# 1500015_ICLED_Featherwing_HW-V1-0.net
KiCad netlist of a schematic drawn in EAGLE
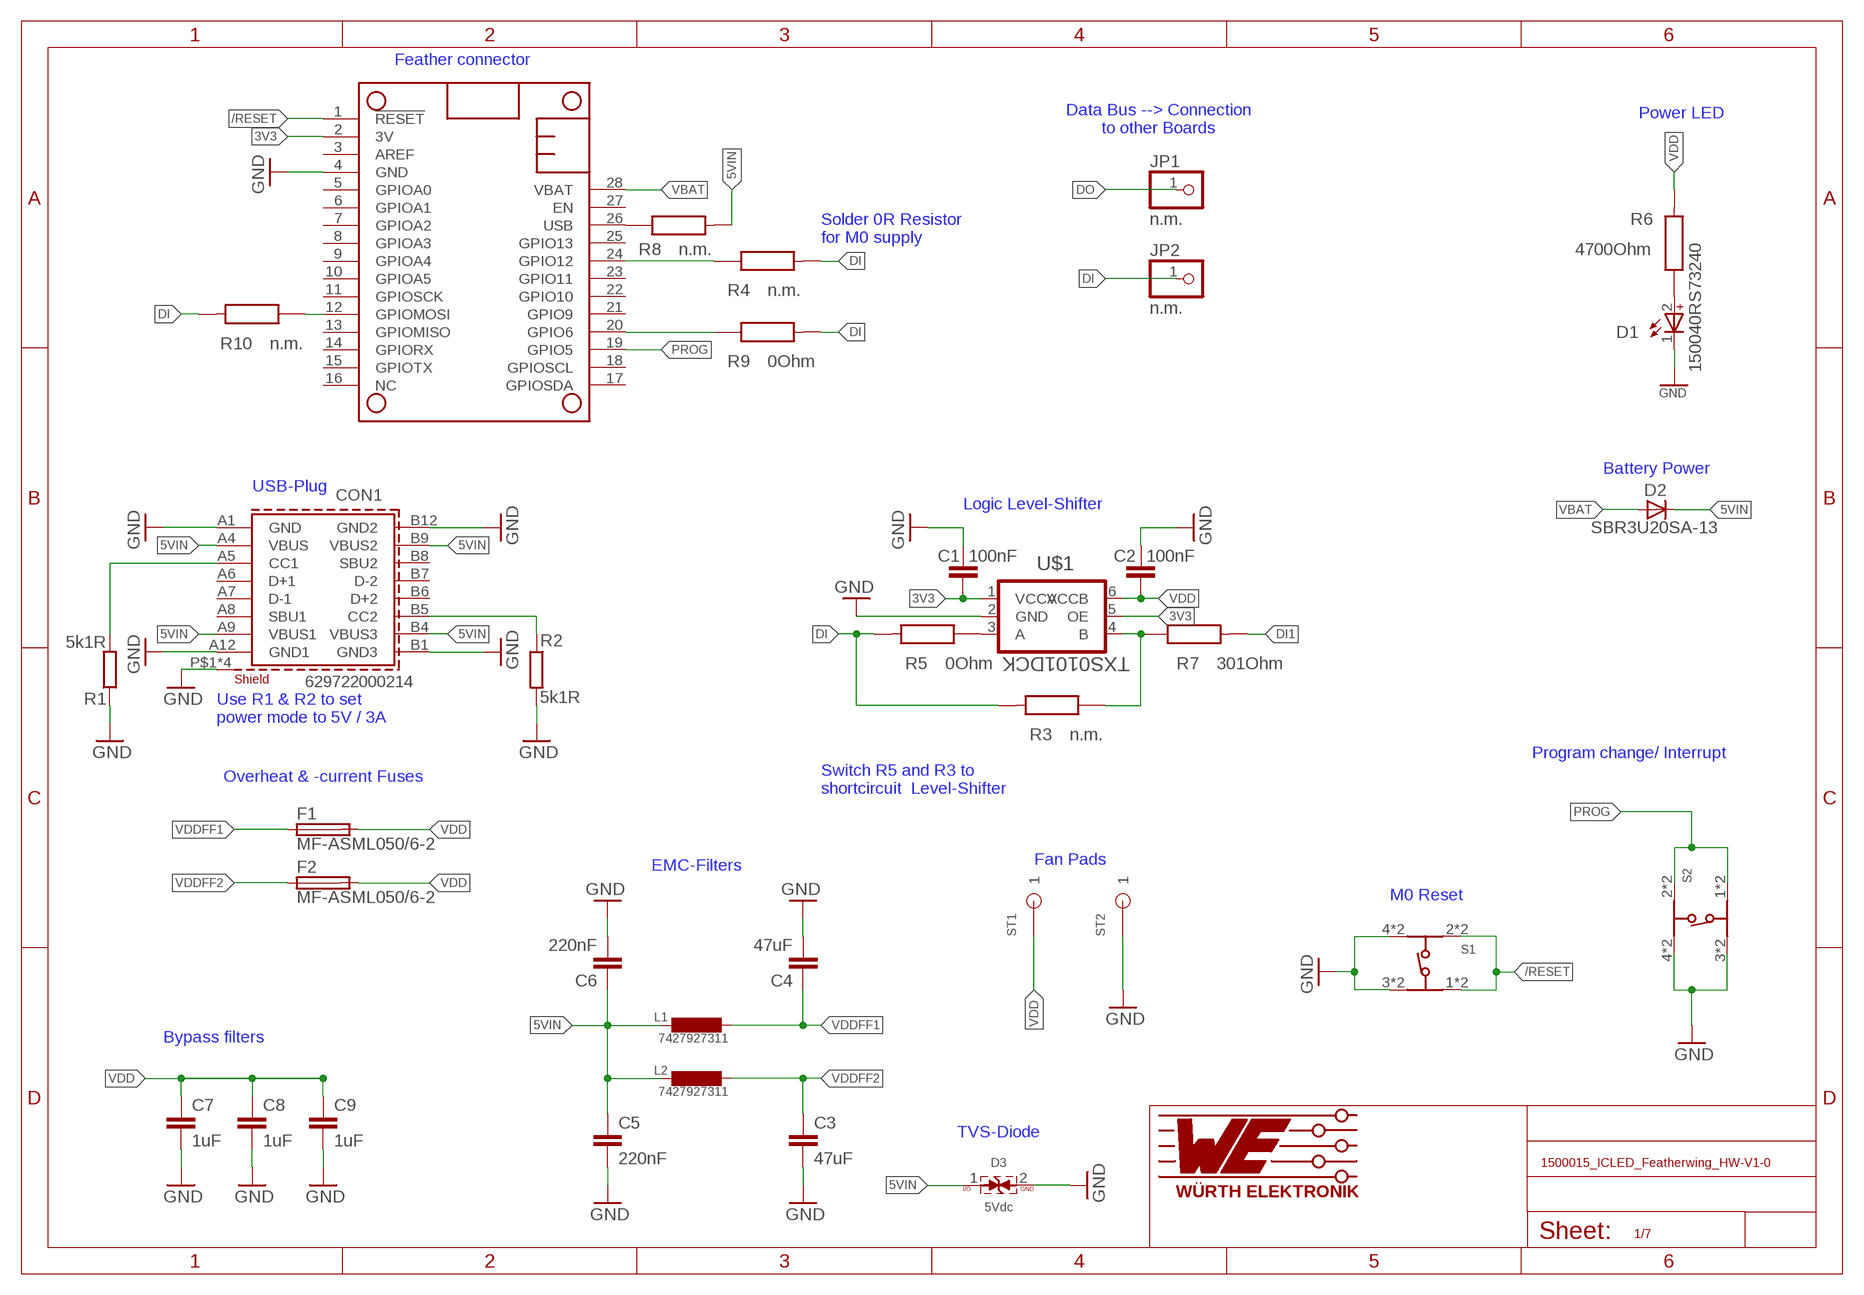
[diagram p0: schematic, sheet 1]
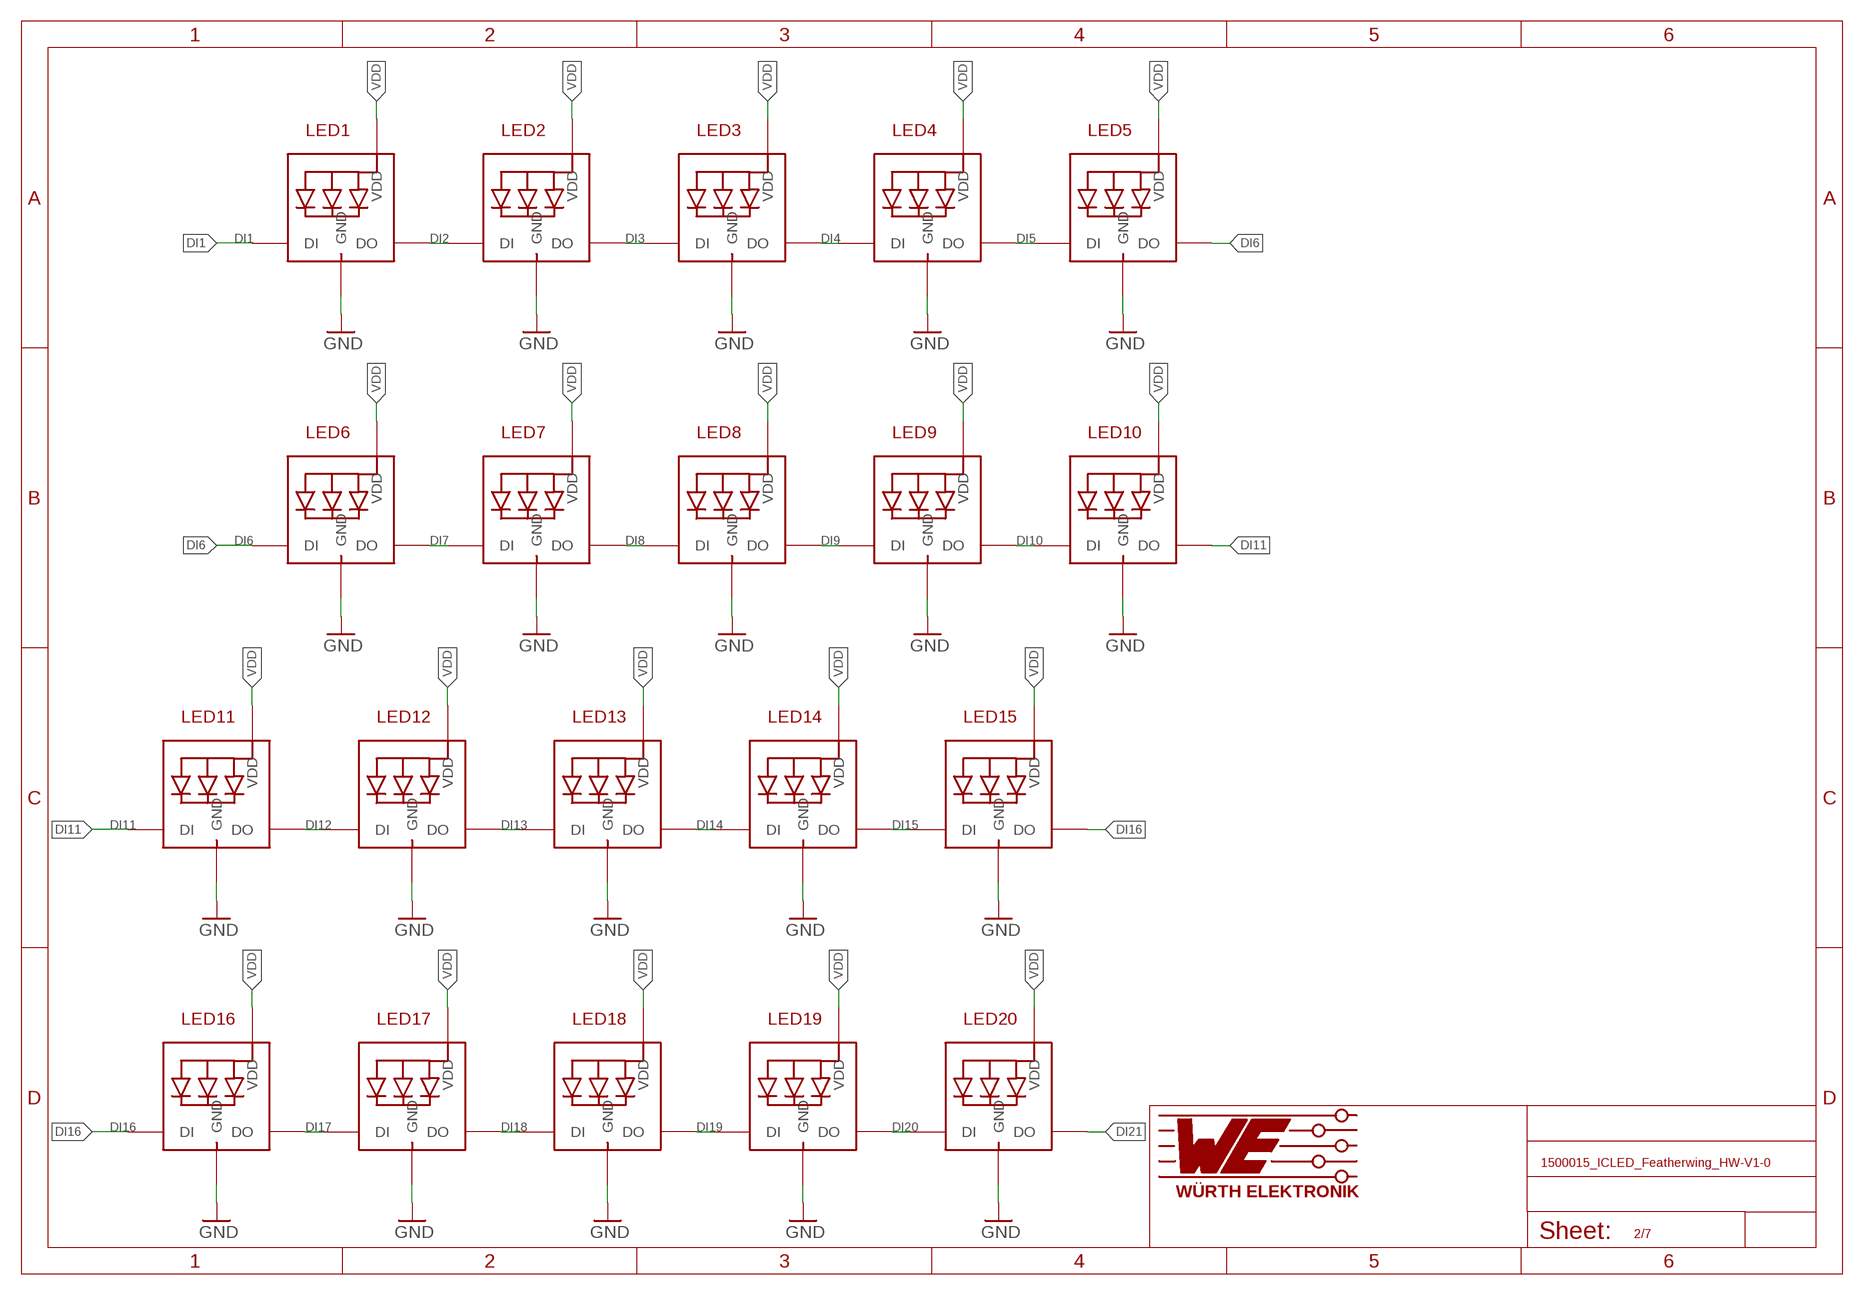
[diagram p1: schematic, sheet 2]
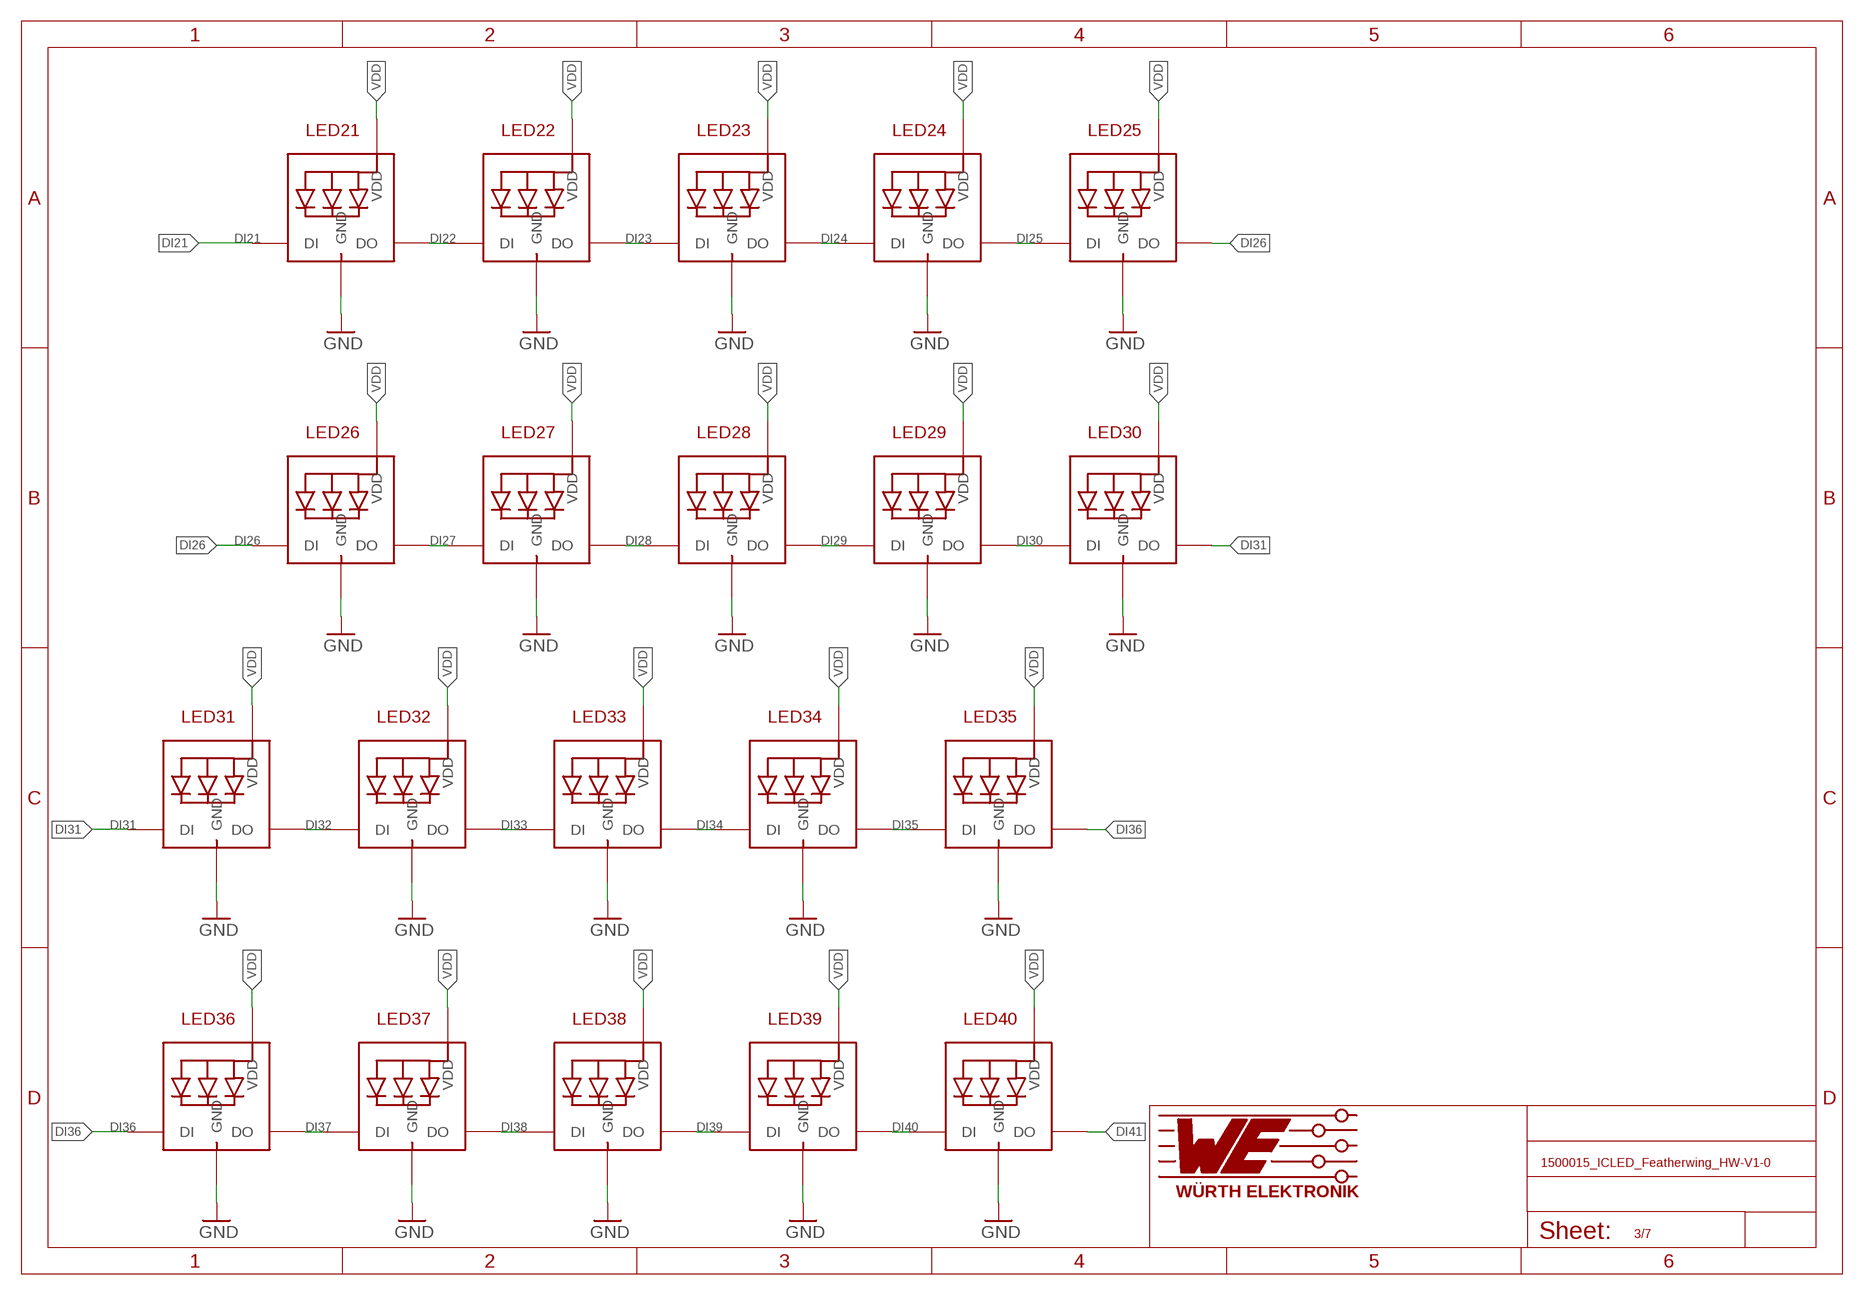
[diagram p2: schematic, sheet 3]
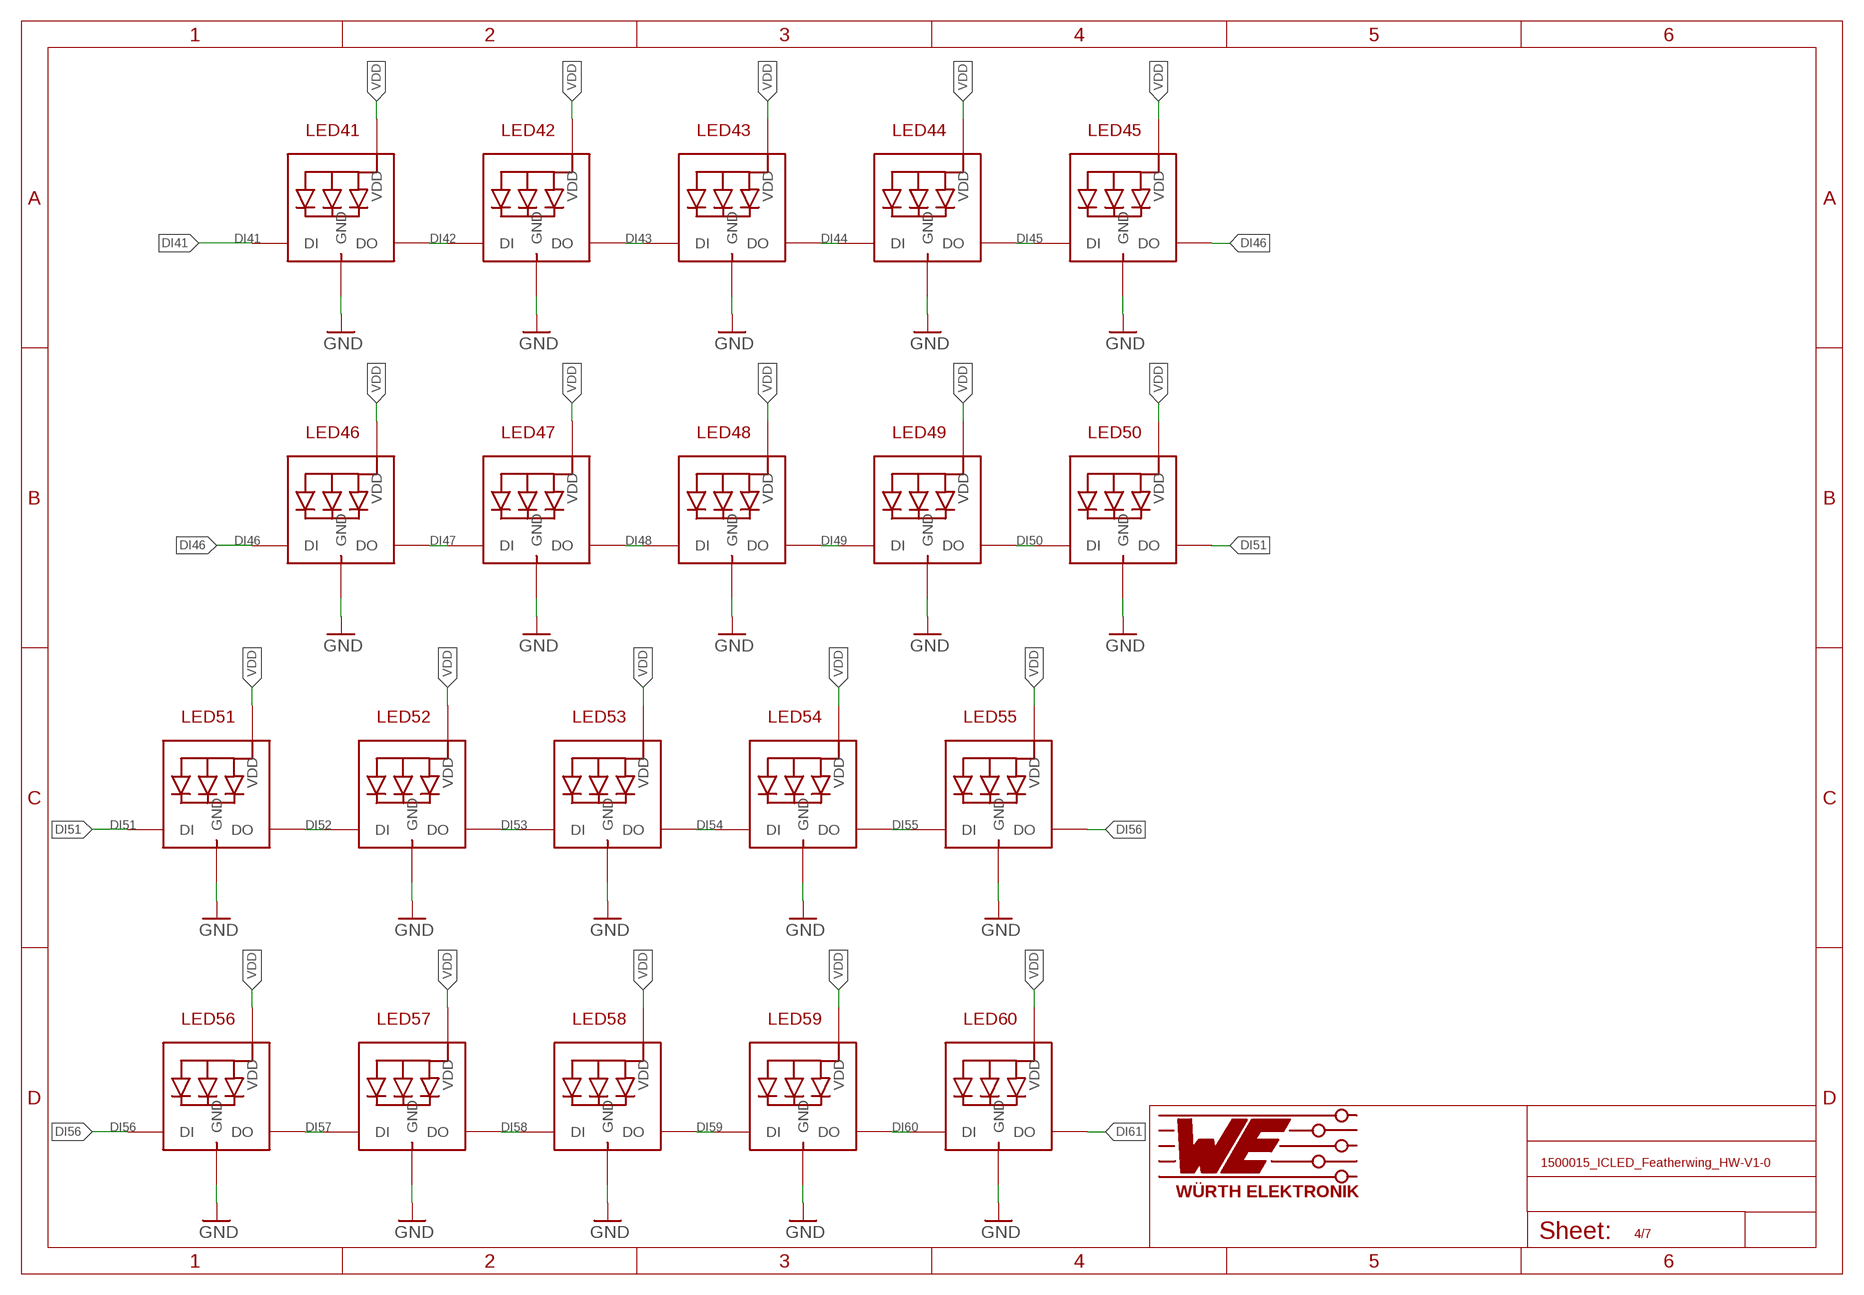
[diagram p3: schematic, sheet 4]
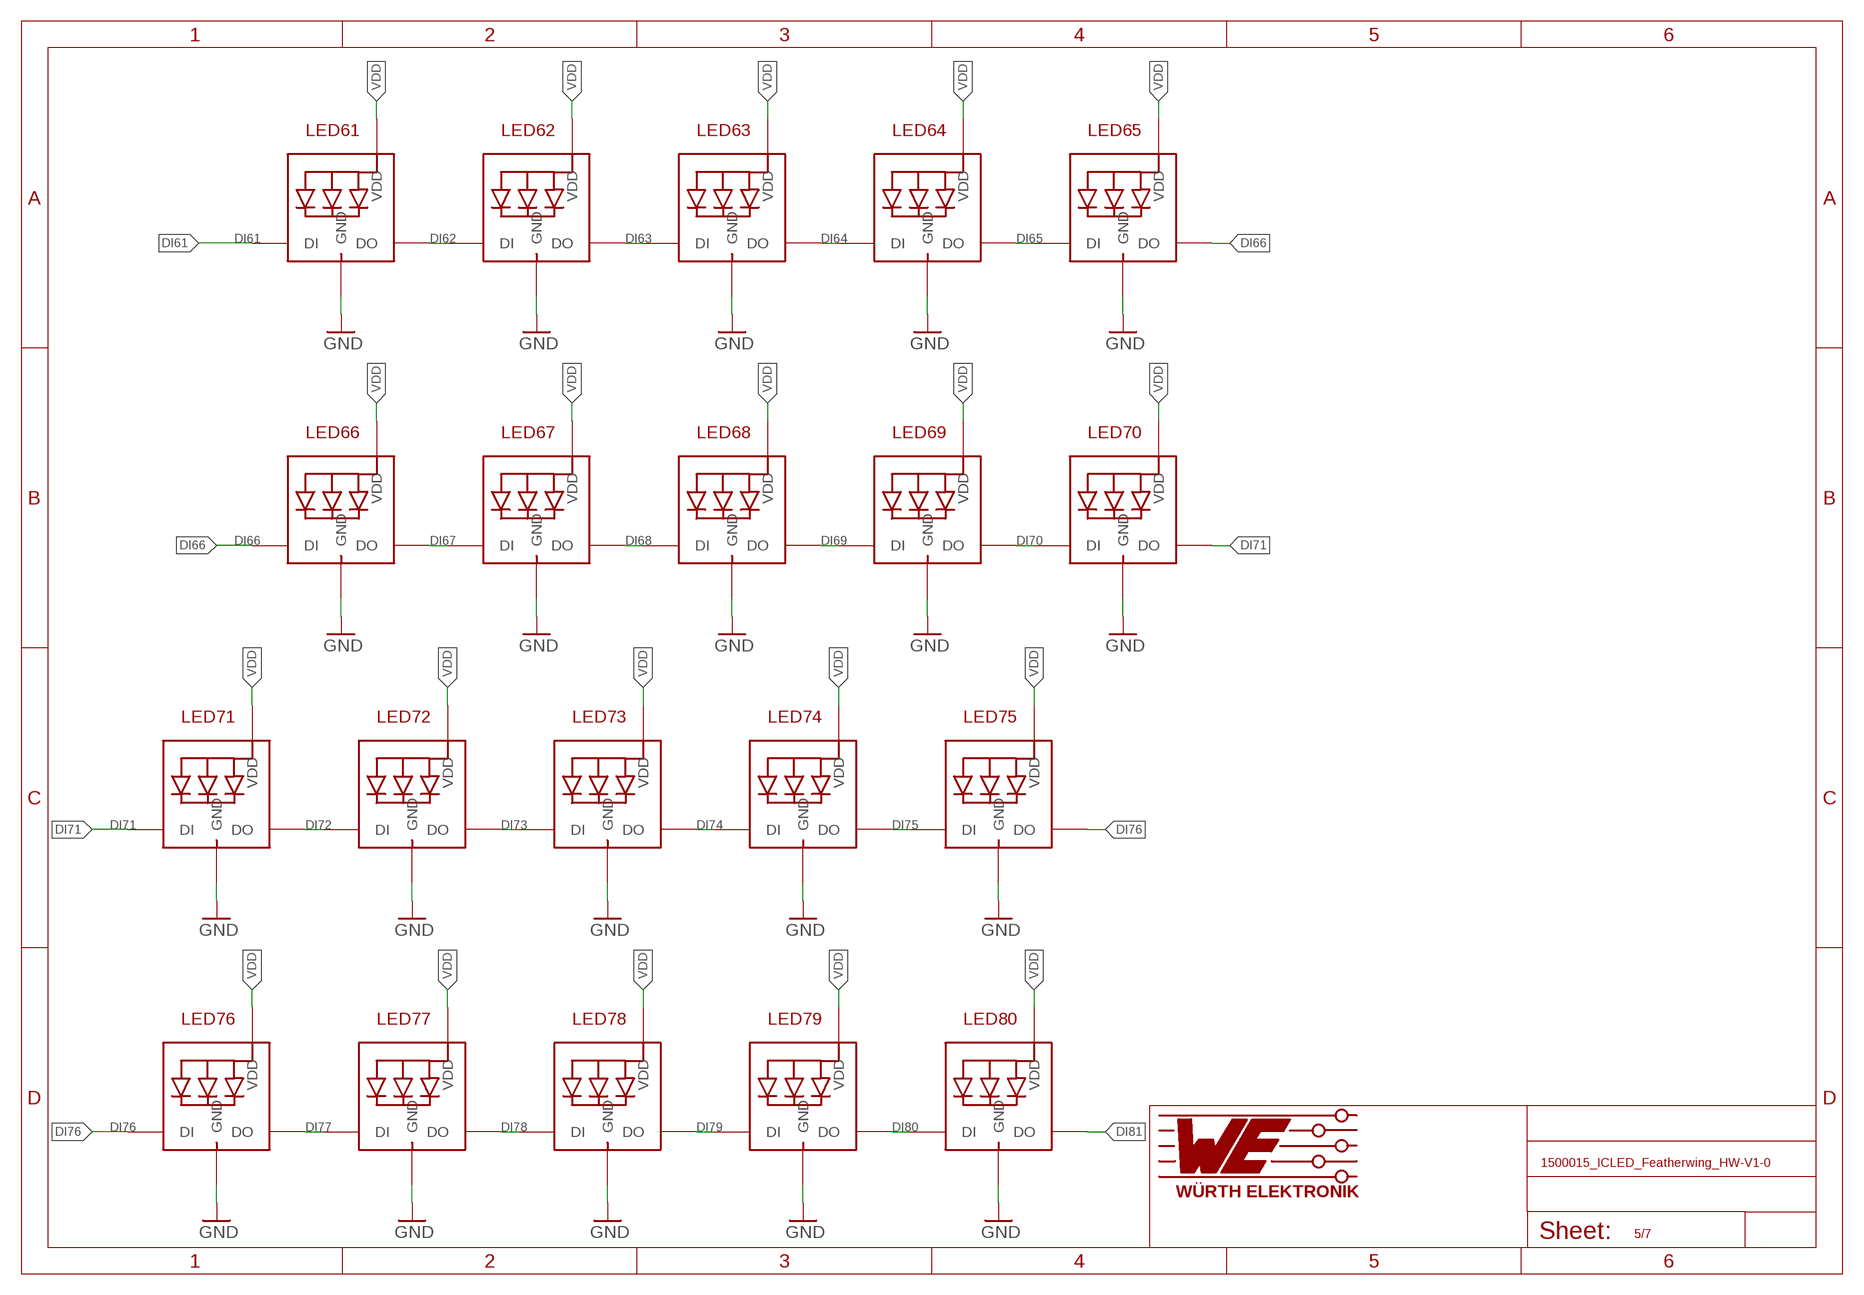
[diagram p4: schematic, sheet 5]
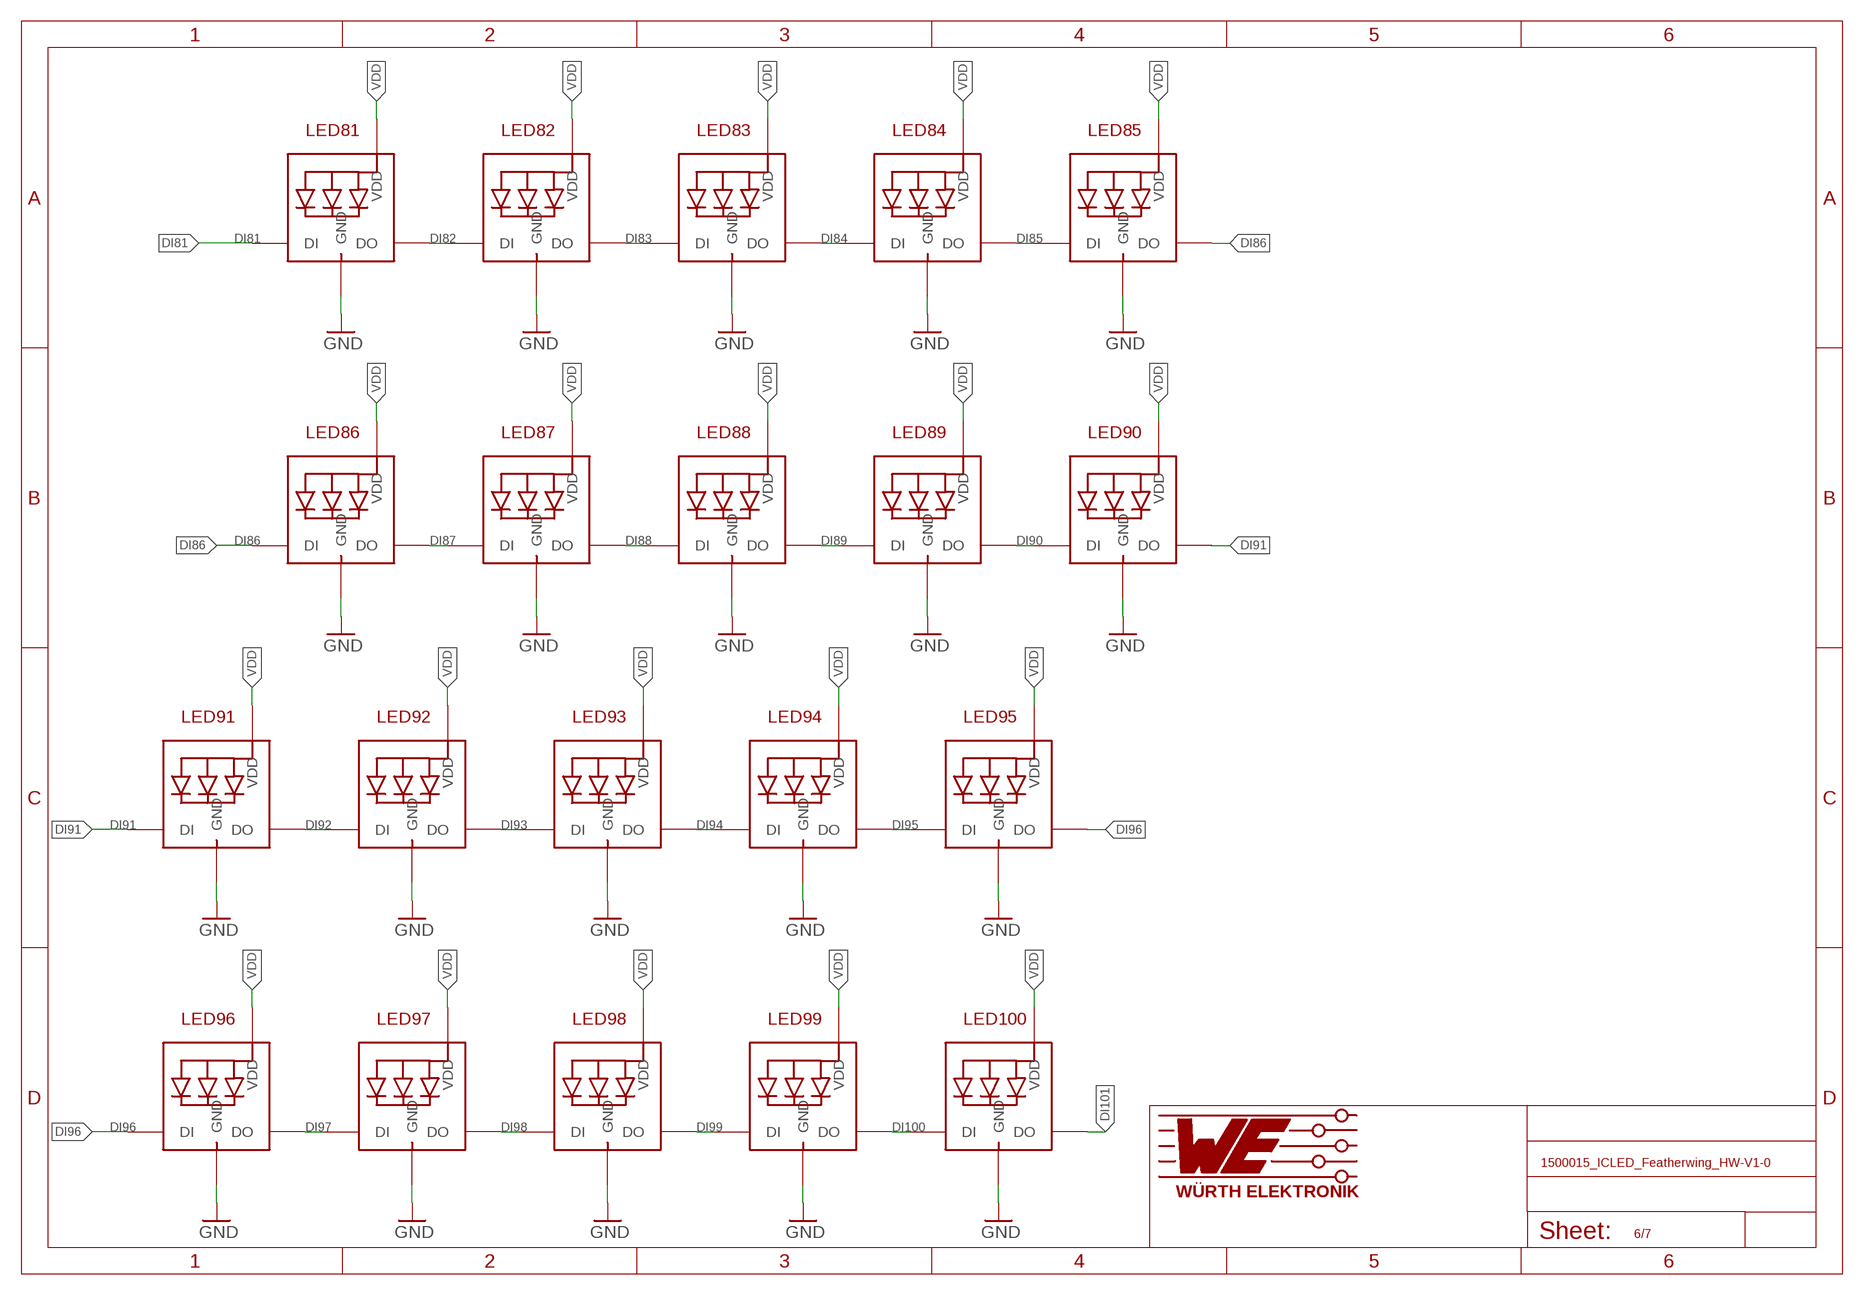
[diagram p5: schematic, sheet 6]
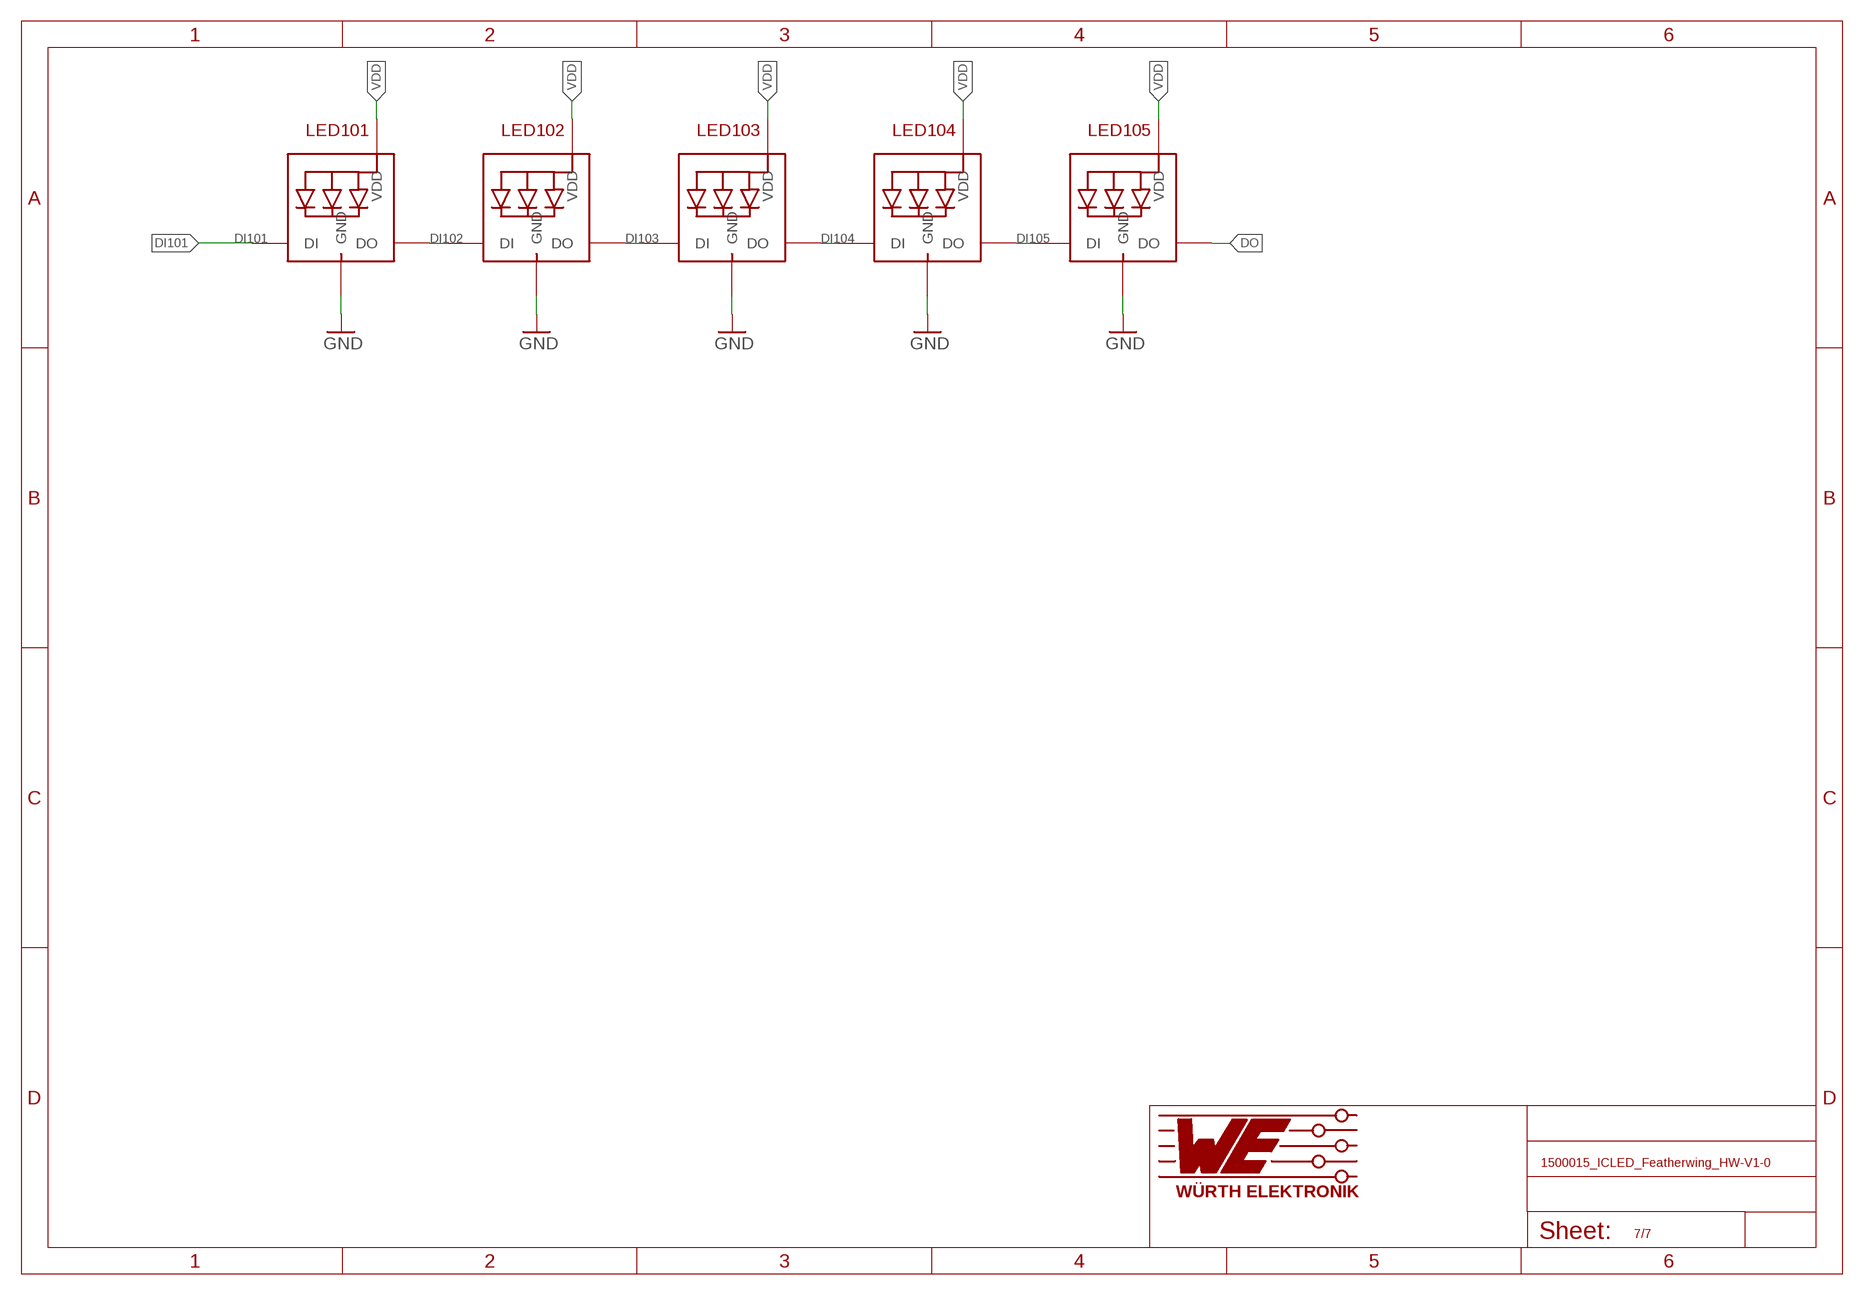
[diagram p6: schematic, sheet 7]

(export (version "E")
  (design (tool "Eeschema 10.0.6"))
  (components
    (comp (ref "LED41")
      (value "1312020030000")
      (footprint "eagle-import:1312020030000_FWANGEPASST")
      (fields (field (name "MANUFACTURER") "Würth Elektronik"))
      (libsource (lib "eagle-import") (part "1312020030000"))
    )
    (comp (ref "LED42")
      (value "1312020030000")
      (footprint "eagle-import:1312020030000_FWANGEPASST")
      (fields (field (name "MANUFACTURER") "Würth Elektronik"))
      (libsource (lib "eagle-import") (part "1312020030000"))
    )
    (comp (ref "LED43")
      (value "1312020030000")
      (footprint "eagle-import:1312020030000_FWANGEPASST")
      (fields (field (name "MANUFACTURER") "Würth Elektronik"))
      (libsource (lib "eagle-import") (part "1312020030000"))
    )
    (comp (ref "LED44")
      (value "1312020030000")
      (footprint "eagle-import:1312020030000_FWANGEPASST")
      (fields (field (name "MANUFACTURER") "Würth Elektronik"))
      (libsource (lib "eagle-import") (part "1312020030000"))
    )
    (comp (ref "LED45")
      (value "1312020030000")
      (footprint "eagle-import:1312020030000_FWANGEPASST")
      (fields (field (name "MANUFACTURER") "Würth Elektronik"))
      (libsource (lib "eagle-import") (part "1312020030000"))
    )
    (comp (ref "LED46")
      (value "1312020030000")
      (footprint "eagle-import:1312020030000_FWANGEPASST")
      (fields (field (name "MANUFACTURER") "Würth Elektronik"))
      (libsource (lib "eagle-import") (part "1312020030000"))
    )
    (comp (ref "LED47")
      (value "1312020030000")
      (footprint "eagle-import:1312020030000_FWANGEPASST")
      (fields (field (name "MANUFACTURER") "Würth Elektronik"))
      (libsource (lib "eagle-import") (part "1312020030000"))
    )
    (comp (ref "LED48")
      (value "1312020030000")
      (footprint "eagle-import:1312020030000_FWANGEPASST")
      (fields (field (name "MANUFACTURER") "Würth Elektronik"))
      (libsource (lib "eagle-import") (part "1312020030000"))
    )
    (comp (ref "LED49")
      (value "1312020030000")
      (footprint "eagle-import:1312020030000_FWANGEPASST")
      (fields (field (name "MANUFACTURER") "Würth Elektronik"))
      (libsource (lib "eagle-import") (part "1312020030000"))
    )
    (comp (ref "LED50")
      (value "1312020030000")
      (footprint "eagle-import:1312020030000_FWANGEPASST")
      (fields (field (name "MANUFACTURER") "Würth Elektronik"))
      (libsource (lib "eagle-import") (part "1312020030000"))
    )
    (comp (ref "LED51")
      (value "1312020030000")
      (footprint "eagle-import:1312020030000_FWANGEPASST")
      (fields (field (name "MANUFACTURER") "Würth Elektronik"))
      (libsource (lib "eagle-import") (part "1312020030000"))
    )
    (comp (ref "LED52")
      (value "1312020030000")
      (footprint "eagle-import:1312020030000_FWANGEPASST")
      (fields (field (name "MANUFACTURER") "Würth Elektronik"))
      (libsource (lib "eagle-import") (part "1312020030000"))
    )
    (comp (ref "LED53")
      (value "1312020030000")
      (footprint "eagle-import:1312020030000_FWANGEPASST")
      (fields (field (name "MANUFACTURER") "Würth Elektronik"))
      (libsource (lib "eagle-import") (part "1312020030000"))
    )
    (comp (ref "LED54")
      (value "1312020030000")
      (footprint "eagle-import:1312020030000_FWANGEPASST")
      (fields (field (name "MANUFACTURER") "Würth Elektronik"))
      (libsource (lib "eagle-import") (part "1312020030000"))
    )
    (comp (ref "LED55")
      (value "1312020030000")
      (footprint "eagle-import:1312020030000_FWANGEPASST")
      (fields (field (name "MANUFACTURER") "Würth Elektronik"))
      (libsource (lib "eagle-import") (part "1312020030000"))
    )
    (comp (ref "LED56")
      (value "1312020030000")
      (footprint "eagle-import:1312020030000_FWANGEPASST")
      (fields (field (name "MANUFACTURER") "Würth Elektronik"))
      (libsource (lib "eagle-import") (part "1312020030000"))
    )
    (comp (ref "LED57")
      (value "1312020030000")
      (footprint "eagle-import:1312020030000_FWANGEPASST")
      (fields (field (name "MANUFACTURER") "Würth Elektronik"))
      (libsource (lib "eagle-import") (part "1312020030000"))
    )
    (comp (ref "LED58")
      (value "1312020030000")
      (footprint "eagle-import:1312020030000_FWANGEPASST")
      (fields (field (name "MANUFACTURER") "Würth Elektronik"))
      (libsource (lib "eagle-import") (part "1312020030000"))
    )
    (comp (ref "LED59")
      (value "1312020030000")
      (footprint "eagle-import:1312020030000_FWANGEPASST")
      (fields (field (name "MANUFACTURER") "Würth Elektronik"))
      (libsource (lib "eagle-import") (part "1312020030000"))
    )
    (comp (ref "LED60")
      (value "1312020030000")
      (footprint "eagle-import:1312020030000_FWANGEPASST")
      (fields (field (name "MANUFACTURER") "Würth Elektronik"))
      (libsource (lib "eagle-import") (part "1312020030000"))
    )
    (comp (ref "LED61")
      (value "1312020030000")
      (footprint "eagle-import:1312020030000_FWANGEPASST")
      (fields (field (name "MANUFACTURER") "Würth Elektronik"))
      (libsource (lib "eagle-import") (part "1312020030000"))
    )
    (comp (ref "LED62")
      (value "1312020030000")
      (footprint "eagle-import:1312020030000_FWANGEPASST")
      (fields (field (name "MANUFACTURER") "Würth Elektronik"))
      (libsource (lib "eagle-import") (part "1312020030000"))
    )
    (comp (ref "LED63")
      (value "1312020030000")
      (footprint "eagle-import:1312020030000_FWANGEPASST")
      (fields (field (name "MANUFACTURER") "Würth Elektronik"))
      (libsource (lib "eagle-import") (part "1312020030000"))
    )
    (comp (ref "LED64")
      (value "1312020030000")
      (footprint "eagle-import:1312020030000_FWANGEPASST")
      (fields (field (name "MANUFACTURER") "Würth Elektronik"))
      (libsource (lib "eagle-import") (part "1312020030000"))
    )
    (comp (ref "LED65")
      (value "1312020030000")
      (footprint "eagle-import:1312020030000_FWANGEPASST")
      (fields (field (name "MANUFACTURER") "Würth Elektronik"))
      (libsource (lib "eagle-import") (part "1312020030000"))
    )
    (comp (ref "LED66")
      (value "1312020030000")
      (footprint "eagle-import:1312020030000_FWANGEPASST")
      (fields (field (name "MANUFACTURER") "Würth Elektronik"))
      (libsource (lib "eagle-import") (part "1312020030000"))
    )
    (comp (ref "LED67")
      (value "1312020030000")
      (footprint "eagle-import:1312020030000_FWANGEPASST")
      (fields (field (name "MANUFACTURER") "Würth Elektronik"))
      (libsource (lib "eagle-import") (part "1312020030000"))
    )
    (comp (ref "LED68")
      (value "1312020030000")
      (footprint "eagle-import:1312020030000_FWANGEPASST")
      (fields (field (name "MANUFACTURER") "Würth Elektronik"))
      (libsource (lib "eagle-import") (part "1312020030000"))
    )
    (comp (ref "LED69")
      (value "1312020030000")
      (footprint "eagle-import:1312020030000_FWANGEPASST")
      (fields (field (name "MANUFACTURER") "Würth Elektronik"))
      (libsource (lib "eagle-import") (part "1312020030000"))
    )
    (comp (ref "LED70")
      (value "1312020030000")
      (footprint "eagle-import:1312020030000_FWANGEPASST")
      (fields (field (name "MANUFACTURER") "Würth Elektronik"))
      (libsource (lib "eagle-import") (part "1312020030000"))
    )
    (comp (ref "LED71")
      (value "1312020030000")
      (footprint "eagle-import:1312020030000_FWANGEPASST")
      (fields (field (name "MANUFACTURER") "Würth Elektronik"))
      (libsource (lib "eagle-import") (part "1312020030000"))
    )
    (comp (ref "LED72")
      (value "1312020030000")
      (footprint "eagle-import:1312020030000_FWANGEPASST")
      (fields (field (name "MANUFACTURER") "Würth Elektronik"))
      (libsource (lib "eagle-import") (part "1312020030000"))
    )
    (comp (ref "LED73")
      (value "1312020030000")
      (footprint "eagle-import:1312020030000_FWANGEPASST")
      (fields (field (name "MANUFACTURER") "Würth Elektronik"))
      (libsource (lib "eagle-import") (part "1312020030000"))
    )
    (comp (ref "LED74")
      (value "1312020030000")
      (footprint "eagle-import:1312020030000_FWANGEPASST")
      (fields (field (name "MANUFACTURER") "Würth Elektronik"))
      (libsource (lib "eagle-import") (part "1312020030000"))
    )
    (comp (ref "LED75")
      (value "1312020030000")
      (footprint "eagle-import:1312020030000_FWANGEPASST")
      (fields (field (name "MANUFACTURER") "Würth Elektronik"))
      (libsource (lib "eagle-import") (part "1312020030000"))
    )
    (comp (ref "LED76")
      (value "1312020030000")
      (footprint "eagle-import:1312020030000_FWANGEPASST")
      (fields (field (name "MANUFACTURER") "Würth Elektronik"))
      (libsource (lib "eagle-import") (part "1312020030000"))
    )
    (comp (ref "LED77")
      (value "1312020030000")
      (footprint "eagle-import:1312020030000_FWANGEPASST")
      (fields (field (name "MANUFACTURER") "Würth Elektronik"))
      (libsource (lib "eagle-import") (part "1312020030000"))
    )
    (comp (ref "LED78")
      (value "1312020030000")
      (footprint "eagle-import:1312020030000_FWANGEPASST")
      (fields (field (name "MANUFACTURER") "Würth Elektronik"))
      (libsource (lib "eagle-import") (part "1312020030000"))
    )
    (comp (ref "LED79")
      (value "1312020030000")
      (footprint "eagle-import:1312020030000_FWANGEPASST")
      (fields (field (name "MANUFACTURER") "Würth Elektronik"))
      (libsource (lib "eagle-import") (part "1312020030000"))
    )
    (comp (ref "LED80")
      (value "1312020030000")
      (footprint "eagle-import:1312020030000_FWANGEPASST")
      (fields (field (name "MANUFACTURER") "Würth Elektronik"))
      (libsource (lib "eagle-import") (part "1312020030000"))
    )
    (comp (ref "C1")
      (value "100nF")
      (footprint "eagle-import:C0402_IPC")
      (fields (field (name "MANUFACTURER") "Würth Elektronik"))
      (libsource (lib "eagle-import") (part "C0402_IPC100NF"))
    )
    (comp (ref "C2")
      (value "100nF")
      (footprint "eagle-import:C0402_IPC")
      (fields (field (name "MANUFACTURER") "Würth Elektronik"))
      (libsource (lib "eagle-import") (part "C0402_IPC100NF"))
    )
    (comp (ref "C3")
      (value "47uF")
      (footprint "eagle-import:C0805")
      (fields
        (field (name "MANUFACTURER") "Würth Elektronik")
        (field (name "NR") "885012107006")
        (field (name "SPG") "6.3V")
      )
      (libsource (lib "eagle-import") (part "C0805"))
    )
    (comp (ref "C4")
      (value "47uF")
      (footprint "eagle-import:C0805")
      (fields
        (field (name "MANUFACTURER") "Würth Elektronik")
        (field (name "NR") "885012107006")
        (field (name "SPG") "6.3V")
      )
      (libsource (lib "eagle-import") (part "C0805"))
    )
    (comp (ref "C5")
      (value "220nF")
      (footprint "eagle-import:C0603_IPC")
      (fields
        (field (name "MANUFACTURER") "Wurth Elektronik")
        (field (name "NR") "885012206125")
        (field (name "SPG") "50V")
        (field (name "TOL") "5%")
      )
      (libsource (lib "eagle-import") (part "C0603_IPC220N"))
    )
    (comp (ref "C6")
      (value "220nF")
      (footprint "eagle-import:C0603_IPC")
      (fields
        (field (name "MANUFACTURER") "Wurth Elektronik")
        (field (name "NR") "885012206125")
        (field (name "SPG") "50V")
        (field (name "TOL") "5%")
      )
      (libsource (lib "eagle-import") (part "C0603_IPC220N"))
    )
    (comp (ref "C7")
      (value "1uF")
      (footprint "eagle-import:C0402_IPC")
      (fields (field (name "MANUFACTURER") "Würth Elektronik"))
      (libsource (lib "eagle-import") (part "C0402_IPC1UF"))
    )
    (comp (ref "C8")
      (value "1uF")
      (footprint "eagle-import:C0402_IPC")
      (fields (field (name "MANUFACTURER") "Würth Elektronik"))
      (libsource (lib "eagle-import") (part "C0402_IPC1UF"))
    )
    (comp (ref "C9")
      (value "1uF")
      (footprint "eagle-import:C0402_IPC")
      (fields (field (name "MANUFACTURER") "Würth Elektronik"))
      (libsource (lib "eagle-import") (part "C0402_IPC1UF"))
    )
    (comp (ref "CON1")
      (value "629722000214")
      (footprint "eagle-import:629722000214")
      (libsource (lib "eagle-import") (part "629722000214"))
    )
    (comp (ref "D1")
      (value "150040RS73240")
      (footprint "eagle-import:WL-SMCC_0402")
      (libsource (lib "eagle-import") (part "WL-SMCC_0402_150040RS73240"))
    )
    (comp (ref "D2")
      (value "SBR3U20SA-13")
      (footprint "eagle-import:SBR3U20SA")
      (fields (field (name "MANUFACTURER") "Diodes Inc"))
      (libsource (lib "eagle-import") (part "SBR3U20SA-13"))
    )
    (comp (ref "D3")
      (value "5Vdc")
      (footprint "eagle-import:WE-TVS_DFN1610-2L")
      (libsource (lib "eagle-import") (part "WE-TVS_DFN1610-2L_824032815"))
    )
    (comp (ref "F1")
      (value "MF-ASML050/6-2")
      (footprint "eagle-import:0402")
      (fields (field (name "MANUFACTURER") "Bourns"))
      (libsource (lib "eagle-import") (part "ERB-RD2R00X"))
    )
    (comp (ref "F2")
      (value "MF-ASML050/6-2")
      (footprint "eagle-import:0402")
      (fields (field (name "MANUFACTURER") "Bourns"))
      (libsource (lib "eagle-import") (part "ERB-RD2R00X"))
    )
    (comp (ref "JP1")
      (value "n.m.")
      (footprint "eagle-import:1X01_R")
      (libsource (lib "eagle-import") (part "PINHD-1X1/R"))
    )
    (comp (ref "JP2")
      (value "n.m.")
      (footprint "eagle-import:1X01_R")
      (libsource (lib "eagle-import") (part "PINHD-1X1/R"))
    )
    (comp (ref "L1")
      (value "7427927311")
      (footprint "eagle-import:L0402_WE_FERRIT")
      (fields (field (name "MANUFACTURER") "Würth Elektronik "))
      (libsource (lib "eagle-import") (part "LL0402_WE_FERRIT"))
    )
    (comp (ref "L2")
      (value "7427927311")
      (footprint "eagle-import:L0402_WE_FERRIT")
      (fields (field (name "MANUFACTURER") "Würth Elektronik "))
      (libsource (lib "eagle-import") (part "LL0402_WE_FERRIT"))
    )
    (comp (ref "MS1")
      (value "FEATHERWING")
      (footprint "eagle-import:FEATHERWING")
      (libsource (lib "eagle-import") (part "FEATHERWING"))
    )
    (comp (ref "R1")
      (value "5k1R")
      (footprint "eagle-import:R0402_IPC")
      (fields (field (name "NR") " RC0402FR-075K1L"))
      (libsource (lib "eagle-import") (part "R0402_IPC10KR"))
    )
    (comp (ref "R2")
      (value "5k1R")
      (footprint "eagle-import:R0402_IPC")
      (fields (field (name "NR") " RC0402FR-075K1L"))
      (libsource (lib "eagle-import") (part "R0402_IPC10KR"))
    )
    (comp (ref "R3")
      (value "n.m.")
      (footprint "eagle-import:WRIS-RSKS_0603_WAVE")
      (libsource (lib "eagle-import") (part "WRIS-RSKS_0603_WAVE_560112116001"))
    )
    (comp (ref "R4")
      (value "n.m.")
      (footprint "eagle-import:WRIS-RSKS_0402")
      (libsource (lib "eagle-import") (part "WRIS-RSKS_0402_560112110001"))
    )
    (comp (ref "R5")
      (value "0Ohm")
      (footprint "eagle-import:WRIS-RSKS_0603_WAVE")
      (libsource (lib "eagle-import") (part "WRIS-RSKS_0603_WAVE_560112116001"))
    )
    (comp (ref "R6")
      (value "4700Ohm")
      (footprint "eagle-import:WRIS-RSKS_0402")
      (libsource (lib "eagle-import") (part "WRIS-RSKS_0402_560112110245"))
    )
    (comp (ref "R7")
      (value "301Ohm")
      (footprint "eagle-import:WRIS-RSKS_0402")
      (libsource (lib "eagle-import") (part "WRIS-RSKS_0402_560112110092"))
    )
    (comp (ref "R8")
      (value "n.m.")
      (footprint "eagle-import:WRIS-RSKS_0402")
      (libsource (lib "eagle-import") (part "WRIS-RSKS_0402_560112110001"))
    )
    (comp (ref "R9")
      (value "0Ohm")
      (footprint "eagle-import:WRIS-RSKS_0603_WAVE")
      (libsource (lib "eagle-import") (part "WRIS-RSKS_0603_WAVE_560112116001"))
    )
    (comp (ref "R10")
      (value "n.m.")
      (footprint "eagle-import:WRIS-RSKS_0603_WAVE")
      (libsource (lib "eagle-import") (part "WRIS-RSKS_0603_WAVE_560112116001"))
    )
    (comp (ref "S1")
      (value "434331013822")
      (footprint "eagle-import:434331013822_ICLEDFW_ANGEPASST")
      (fields (field (name "MANUFACTURER") "Würth Elektronik"))
      (libsource (lib "eagle-import") (part "434331013822_ANGEPASST"))
    )
    (comp (ref "S2")
      (value "434331013822")
      (footprint "eagle-import:434331013822_ICLEDFW_ANGEPASST")
      (fields (field (name "MANUFACTURER") "Würth Elektronik"))
      (libsource (lib "eagle-import") (part "434331013822_ANGEPASST"))
    )
    (comp (ref "ST1")
      (value "1_5X1MM")
      (footprint "eagle-import:1_5X1MM")
      (libsource (lib "eagle-import") (part "1_5X1MM"))
    )
    (comp (ref "ST2")
      (value "1_5X1MM")
      (footprint "eagle-import:1_5X1MM")
      (libsource (lib "eagle-import") (part "1_5X1MM"))
    )
    (comp (ref "U$1")
      (value "TXS0101DCK")
      (footprint "eagle-import:SC70")
      (fields (field (name "MANUFACTURER") "Texas Instruments"))
      (libsource (lib "eagle-import") (part "TXS0101DCK"))
    )
    (comp (ref "LED21")
      (value "1312020030000")
      (footprint "eagle-import:1312020030000_FWANGEPASST")
      (fields (field (name "MANUFACTURER") "Würth Elektronik"))
      (libsource (lib "eagle-import") (part "1312020030000"))
    )
    (comp (ref "LED22")
      (value "1312020030000")
      (footprint "eagle-import:1312020030000_FWANGEPASST")
      (fields (field (name "MANUFACTURER") "Würth Elektronik"))
      (libsource (lib "eagle-import") (part "1312020030000"))
    )
    (comp (ref "LED23")
      (value "1312020030000")
      (footprint "eagle-import:1312020030000_FWANGEPASST")
      (fields (field (name "MANUFACTURER") "Würth Elektronik"))
      (libsource (lib "eagle-import") (part "1312020030000"))
    )
    (comp (ref "LED24")
      (value "1312020030000")
      (footprint "eagle-import:1312020030000_FWANGEPASST")
      (fields (field (name "MANUFACTURER") "Würth Elektronik"))
      (libsource (lib "eagle-import") (part "1312020030000"))
    )
    (comp (ref "LED25")
      (value "1312020030000")
      (footprint "eagle-import:1312020030000_FWANGEPASST")
      (fields (field (name "MANUFACTURER") "Würth Elektronik"))
      (libsource (lib "eagle-import") (part "1312020030000"))
    )
    (comp (ref "LED26")
      (value "1312020030000")
      (footprint "eagle-import:1312020030000_FWANGEPASST")
      (fields (field (name "MANUFACTURER") "Würth Elektronik"))
      (libsource (lib "eagle-import") (part "1312020030000"))
    )
    (comp (ref "LED27")
      (value "1312020030000")
      (footprint "eagle-import:1312020030000_FWANGEPASST")
      (fields (field (name "MANUFACTURER") "Würth Elektronik"))
      (libsource (lib "eagle-import") (part "1312020030000"))
    )
    (comp (ref "LED28")
      (value "1312020030000")
      (footprint "eagle-import:1312020030000_FWANGEPASST")
      (fields (field (name "MANUFACTURER") "Würth Elektronik"))
      (libsource (lib "eagle-import") (part "1312020030000"))
    )
    (comp (ref "LED29")
      (value "1312020030000")
      (footprint "eagle-import:1312020030000_FWANGEPASST")
      (fields (field (name "MANUFACTURER") "Würth Elektronik"))
      (libsource (lib "eagle-import") (part "1312020030000"))
    )
    (comp (ref "LED30")
      (value "1312020030000")
      (footprint "eagle-import:1312020030000_FWANGEPASST")
      (fields (field (name "MANUFACTURER") "Würth Elektronik"))
      (libsource (lib "eagle-import") (part "1312020030000"))
    )
    (comp (ref "LED31")
      (value "1312020030000")
      (footprint "eagle-import:1312020030000_FWANGEPASST")
      (fields (field (name "MANUFACTURER") "Würth Elektronik"))
      (libsource (lib "eagle-import") (part "1312020030000"))
    )
    (comp (ref "LED32")
      (value "1312020030000")
      (footprint "eagle-import:1312020030000_FWANGEPASST")
      (fields (field (name "MANUFACTURER") "Würth Elektronik"))
      (libsource (lib "eagle-import") (part "1312020030000"))
    )
    (comp (ref "LED33")
      (value "1312020030000")
      (footprint "eagle-import:1312020030000_FWANGEPASST")
      (fields (field (name "MANUFACTURER") "Würth Elektronik"))
      (libsource (lib "eagle-import") (part "1312020030000"))
    )
    (comp (ref "LED34")
      (value "1312020030000")
      (footprint "eagle-import:1312020030000_FWANGEPASST")
      (fields (field (name "MANUFACTURER") "Würth Elektronik"))
      (libsource (lib "eagle-import") (part "1312020030000"))
    )
    (comp (ref "LED35")
      (value "1312020030000")
      (footprint "eagle-import:1312020030000_FWANGEPASST")
      (fields (field (name "MANUFACTURER") "Würth Elektronik"))
      (libsource (lib "eagle-import") (part "1312020030000"))
    )
    (comp (ref "LED36")
      (value "1312020030000")
      (footprint "eagle-import:1312020030000_FWANGEPASST")
      (fields (field (name "MANUFACTURER") "Würth Elektronik"))
      (libsource (lib "eagle-import") (part "1312020030000"))
    )
    (comp (ref "LED37")
      (value "1312020030000")
      (footprint "eagle-import:1312020030000_FWANGEPASST")
      (fields (field (name "MANUFACTURER") "Würth Elektronik"))
      (libsource (lib "eagle-import") (part "1312020030000"))
    )
    (comp (ref "LED38")
      (value "1312020030000")
      (footprint "eagle-import:1312020030000_FWANGEPASST")
      (fields (field (name "MANUFACTURER") "Würth Elektronik"))
      (libsource (lib "eagle-import") (part "1312020030000"))
    )
    (comp (ref "LED39")
      (value "1312020030000")
      (footprint "eagle-import:1312020030000_FWANGEPASST")
      (fields (field (name "MANUFACTURER") "Würth Elektronik"))
      (libsource (lib "eagle-import") (part "1312020030000"))
    )
    (comp (ref "LED40")
      (value "1312020030000")
      (footprint "eagle-import:1312020030000_FWANGEPASST")
      (fields (field (name "MANUFACTURER") "Würth Elektronik"))
      (libsource (lib "eagle-import") (part "1312020030000"))
    )
    (comp (ref "LED101")
      (value "1312020030000")
      (footprint "eagle-import:1312020030000_FWANGEPASST")
      (fields (field (name "MANUFACTURER") "Würth Elektronik"))
      (libsource (lib "eagle-import") (part "1312020030000"))
    )
    (comp (ref "LED102")
      (value "1312020030000")
      (footprint "eagle-import:1312020030000_FWANGEPASST")
      (fields (field (name "MANUFACTURER") "Würth Elektronik"))
      (libsource (lib "eagle-import") (part "1312020030000"))
    )
    (comp (ref "LED103")
      (value "1312020030000")
      (footprint "eagle-import:1312020030000_FWANGEPASST")
      (fields (field (name "MANUFACTURER") "Würth Elektronik"))
      (libsource (lib "eagle-import") (part "1312020030000"))
    )
    (comp (ref "LED104")
      (value "1312020030000")
      (footprint "eagle-import:1312020030000_FWANGEPASST")
      (fields (field (name "MANUFACTURER") "Würth Elektronik"))
      (libsource (lib "eagle-import") (part "1312020030000"))
    )
    (comp (ref "LED105")
      (value "1312020030000")
      (footprint "eagle-import:1312020030000_FWANGEPASST")
      (fields (field (name "MANUFACTURER") "Würth Elektronik"))
      (libsource (lib "eagle-import") (part "1312020030000"))
    )
    (comp (ref "LED1")
      (value "1312020030000")
      (footprint "eagle-import:1312020030000_FWANGEPASST")
      (fields (field (name "MANUFACTURER") "Würth Elektronik"))
      (libsource (lib "eagle-import") (part "1312020030000"))
    )
    (comp (ref "LED2")
      (value "1312020030000")
      (footprint "eagle-import:1312020030000_FWANGEPASST")
      (fields (field (name "MANUFACTURER") "Würth Elektronik"))
      (libsource (lib "eagle-import") (part "1312020030000"))
    )
    (comp (ref "LED3")
      (value "1312020030000")
      (footprint "eagle-import:1312020030000_FWANGEPASST")
      (fields (field (name "MANUFACTURER") "Würth Elektronik"))
      (libsource (lib "eagle-import") (part "1312020030000"))
    )
    (comp (ref "LED4")
      (value "1312020030000")
      (footprint "eagle-import:1312020030000_FWANGEPASST")
      (fields (field (name "MANUFACTURER") "Würth Elektronik"))
      (libsource (lib "eagle-import") (part "1312020030000"))
    )
    (comp (ref "LED5")
      (value "1312020030000")
      (footprint "eagle-import:1312020030000_FWANGEPASST")
      (fields (field (name "MANUFACTURER") "Würth Elektronik"))
      (libsource (lib "eagle-import") (part "1312020030000"))
    )
    (comp (ref "LED6")
      (value "1312020030000")
      (footprint "eagle-import:1312020030000_FWANGEPASST")
      (fields (field (name "MANUFACTURER") "Würth Elektronik"))
      (libsource (lib "eagle-import") (part "1312020030000"))
    )
    (comp (ref "LED7")
      (value "1312020030000")
      (footprint "eagle-import:1312020030000_FWANGEPASST")
      (fields (field (name "MANUFACTURER") "Würth Elektronik"))
      (libsource (lib "eagle-import") (part "1312020030000"))
    )
    (comp (ref "LED8")
      (value "1312020030000")
      (footprint "eagle-import:1312020030000_FWANGEPASST")
      (fields (field (name "MANUFACTURER") "Würth Elektronik"))
      (libsource (lib "eagle-import") (part "1312020030000"))
    )
    (comp (ref "LED9")
      (value "1312020030000")
      (footprint "eagle-import:1312020030000_FWANGEPASST")
      (fields (field (name "MANUFACTURER") "Würth Elektronik"))
      (libsource (lib "eagle-import") (part "1312020030000"))
    )
    (comp (ref "LED10")
      (value "1312020030000")
      (footprint "eagle-import:1312020030000_FWANGEPASST")
      (fields (field (name "MANUFACTURER") "Würth Elektronik"))
      (libsource (lib "eagle-import") (part "1312020030000"))
    )
    (comp (ref "LED11")
      (value "1312020030000")
      (footprint "eagle-import:1312020030000_FWANGEPASST")
      (fields (field (name "MANUFACTURER") "Würth Elektronik"))
      (libsource (lib "eagle-import") (part "1312020030000"))
    )
    (comp (ref "LED12")
      (value "1312020030000")
      (footprint "eagle-import:1312020030000_FWANGEPASST")
      (fields (field (name "MANUFACTURER") "Würth Elektronik"))
      (libsource (lib "eagle-import") (part "1312020030000"))
    )
    (comp (ref "LED13")
      (value "1312020030000")
      (footprint "eagle-import:1312020030000_FWANGEPASST")
      (fields (field (name "MANUFACTURER") "Würth Elektronik"))
      (libsource (lib "eagle-import") (part "1312020030000"))
    )
    (comp (ref "LED14")
      (value "1312020030000")
      (footprint "eagle-import:1312020030000_FWANGEPASST")
      (fields (field (name "MANUFACTURER") "Würth Elektronik"))
      (libsource (lib "eagle-import") (part "1312020030000"))
    )
    (comp (ref "LED15")
      (value "1312020030000")
      (footprint "eagle-import:1312020030000_FWANGEPASST")
      (fields (field (name "MANUFACTURER") "Würth Elektronik"))
      (libsource (lib "eagle-import") (part "1312020030000"))
    )
    (comp (ref "LED16")
      (value "1312020030000")
      (footprint "eagle-import:1312020030000_FWANGEPASST")
      (fields (field (name "MANUFACTURER") "Würth Elektronik"))
      (libsource (lib "eagle-import") (part "1312020030000"))
    )
    (comp (ref "LED17")
      (value "1312020030000")
      (footprint "eagle-import:1312020030000_FWANGEPASST")
      (fields (field (name "MANUFACTURER") "Würth Elektronik"))
      (libsource (lib "eagle-import") (part "1312020030000"))
    )
    (comp (ref "LED18")
      (value "1312020030000")
      (footprint "eagle-import:1312020030000_FWANGEPASST")
      (fields (field (name "MANUFACTURER") "Würth Elektronik"))
      (libsource (lib "eagle-import") (part "1312020030000"))
    )
    (comp (ref "LED19")
      (value "1312020030000")
      (footprint "eagle-import:1312020030000_FWANGEPASST")
      (fields (field (name "MANUFACTURER") "Würth Elektronik"))
      (libsource (lib "eagle-import") (part "1312020030000"))
    )
    (comp (ref "LED20")
      (value "1312020030000")
      (footprint "eagle-import:1312020030000_FWANGEPASST")
      (fields (field (name "MANUFACTURER") "Würth Elektronik"))
      (libsource (lib "eagle-import") (part "1312020030000"))
    )
    (comp (ref "LED81")
      (value "1312020030000")
      (footprint "eagle-import:1312020030000_FWANGEPASST")
      (fields (field (name "MANUFACTURER") "Würth Elektronik"))
      (libsource (lib "eagle-import") (part "1312020030000"))
    )
    (comp (ref "LED82")
      (value "1312020030000")
      (footprint "eagle-import:1312020030000_FWANGEPASST")
      (fields (field (name "MANUFACTURER") "Würth Elektronik"))
      (libsource (lib "eagle-import") (part "1312020030000"))
    )
    (comp (ref "LED83")
      (value "1312020030000")
      (footprint "eagle-import:1312020030000_FWANGEPASST")
      (fields (field (name "MANUFACTURER") "Würth Elektronik"))
      (libsource (lib "eagle-import") (part "1312020030000"))
    )
    (comp (ref "LED84")
      (value "1312020030000")
      (footprint "eagle-import:1312020030000_FWANGEPASST")
      (fields (field (name "MANUFACTURER") "Würth Elektronik"))
      (libsource (lib "eagle-import") (part "1312020030000"))
    )
    (comp (ref "LED85")
      (value "1312020030000")
      (footprint "eagle-import:1312020030000_FWANGEPASST")
      (fields (field (name "MANUFACTURER") "Würth Elektronik"))
      (libsource (lib "eagle-import") (part "1312020030000"))
    )
    (comp (ref "LED86")
      (value "1312020030000")
      (footprint "eagle-import:1312020030000_FWANGEPASST")
      (fields (field (name "MANUFACTURER") "Würth Elektronik"))
      (libsource (lib "eagle-import") (part "1312020030000"))
    )
    (comp (ref "LED87")
      (value "1312020030000")
      (footprint "eagle-import:1312020030000_FWANGEPASST")
      (fields (field (name "MANUFACTURER") "Würth Elektronik"))
      (libsource (lib "eagle-import") (part "1312020030000"))
    )
    (comp (ref "LED88")
      (value "1312020030000")
      (footprint "eagle-import:1312020030000_FWANGEPASST")
      (fields (field (name "MANUFACTURER") "Würth Elektronik"))
      (libsource (lib "eagle-import") (part "1312020030000"))
    )
    (comp (ref "LED89")
      (value "1312020030000")
      (footprint "eagle-import:1312020030000_FWANGEPASST")
      (fields (field (name "MANUFACTURER") "Würth Elektronik"))
      (libsource (lib "eagle-import") (part "1312020030000"))
    )
    (comp (ref "LED90")
      (value "1312020030000")
      (footprint "eagle-import:1312020030000_FWANGEPASST")
      (fields (field (name "MANUFACTURER") "Würth Elektronik"))
      (libsource (lib "eagle-import") (part "1312020030000"))
    )
    (comp (ref "LED91")
      (value "1312020030000")
      (footprint "eagle-import:1312020030000_FWANGEPASST")
      (fields (field (name "MANUFACTURER") "Würth Elektronik"))
      (libsource (lib "eagle-import") (part "1312020030000"))
    )
    (comp (ref "LED92")
      (value "1312020030000")
      (footprint "eagle-import:1312020030000_FWANGEPASST")
      (fields (field (name "MANUFACTURER") "Würth Elektronik"))
      (libsource (lib "eagle-import") (part "1312020030000"))
    )
    (comp (ref "LED93")
      (value "1312020030000")
      (footprint "eagle-import:1312020030000_FWANGEPASST")
      (fields (field (name "MANUFACTURER") "Würth Elektronik"))
      (libsource (lib "eagle-import") (part "1312020030000"))
    )
    (comp (ref "LED94")
      (value "1312020030000")
      (footprint "eagle-import:1312020030000_FWANGEPASST")
      (fields (field (name "MANUFACTURER") "Würth Elektronik"))
      (libsource (lib "eagle-import") (part "1312020030000"))
    )
    (comp (ref "LED95")
      (value "1312020030000")
      (footprint "eagle-import:1312020030000_FWANGEPASST")
      (fields (field (name "MANUFACTURER") "Würth Elektronik"))
      (libsource (lib "eagle-import") (part "1312020030000"))
    )
    (comp (ref "LED96")
      (value "1312020030000")
      (footprint "eagle-import:1312020030000_FWANGEPASST")
      (fields (field (name "MANUFACTURER") "Würth Elektronik"))
      (libsource (lib "eagle-import") (part "1312020030000"))
    )
    (comp (ref "LED97")
      (value "1312020030000")
      (footprint "eagle-import:1312020030000_FWANGEPASST")
      (fields (field (name "MANUFACTURER") "Würth Elektronik"))
      (libsource (lib "eagle-import") (part "1312020030000"))
    )
    (comp (ref "LED98")
      (value "1312020030000")
      (footprint "eagle-import:1312020030000_FWANGEPASST")
      (fields (field (name "MANUFACTURER") "Würth Elektronik"))
      (libsource (lib "eagle-import") (part "1312020030000"))
    )
    (comp (ref "LED99")
      (value "1312020030000")
      (footprint "eagle-import:1312020030000_FWANGEPASST")
      (fields (field (name "MANUFACTURER") "Würth Elektronik"))
      (libsource (lib "eagle-import") (part "1312020030000"))
    )
    (comp (ref "LED100")
      (value "1312020030000")
      (footprint "eagle-import:1312020030000_FWANGEPASST")
      (fields (field (name "MANUFACTURER") "Würth Elektronik"))
      (libsource (lib "eagle-import") (part "1312020030000"))
    )
  )
  (nets
    (net (code "1") (name "3V3") (class "Default")
      (node (ref "C1") (pin "2") (pinfunction "2_2") (pintype "passive"))
      (node (ref "MS1") (pin "2") (pinfunction "3V_2") (pintype "power_in"))
      (node (ref "U$1") (pin "1") (pinfunction "VCCA_1") (pintype "input"))
      (node (ref "U$1") (pin "5") (pinfunction "OE_5") (pintype "input"))
    )
    (net (code "2") (name "5VIN") (class "Default")
      (node (ref "C5") (pin "1") (pinfunction "1_1") (pintype "passive"))
      (node (ref "C6") (pin "1") (pinfunction "1_1") (pintype "passive"))
      (node (ref "CON1") (pin "A4") (pinfunction "VBUS_A4") (pintype "passive"))
      (node (ref "CON1") (pin "A9") (pinfunction "VBUS1_A9") (pintype "passive"))
      (node (ref "CON1") (pin "B4") (pinfunction "VBUS3_B4") (pintype "passive"))
      (node (ref "CON1") (pin "B9") (pinfunction "VBUS2_B9") (pintype "passive"))
      (node (ref "D2") (pin "K") (pinfunction "C_K") (pintype "passive"))
      (node (ref "D3") (pin "1") (pinfunction "I/O_1") (pintype "passive"))
      (node (ref "L1") (pin "P$2") (pinfunction "2_P$2") (pintype "passive"))
      (node (ref "L2") (pin "P$2") (pinfunction "2_P$2") (pintype "passive"))
      (node (ref "R8") (pin "2") (pinfunction "2_2") (pintype "passive"))
    )
    (net (code "3") (name "DI") (class "Default")
      (node (ref "JP2") (pin "1") (pinfunction "1_1") (pintype "passive"))
      (node (ref "R10") (pin "2") (pinfunction "2_2") (pintype "passive"))
      (node (ref "R3") (pin "2") (pinfunction "2_2") (pintype "passive"))
      (node (ref "R4") (pin "2") (pinfunction "2_2") (pintype "passive"))
      (node (ref "R5") (pin "2") (pinfunction "2_2") (pintype "passive"))
      (node (ref "R9") (pin "2") (pinfunction "2_2") (pintype "passive"))
    )
    (net (code "4") (name "DI1") (class "Default")
      (node (ref "LED1") (pin "3-DIN") (pinfunction "DI_3-DIN") (pintype "input"))
      (node (ref "R7") (pin "2") (pinfunction "2_2") (pintype "passive"))
    )
    (net (code "5") (name "DI2") (class "Default")
      (node (ref "LED1") (pin "1-DOUT") (pinfunction "DO_1-DOUT") (pintype "output"))
      (node (ref "LED2") (pin "3-DIN") (pinfunction "DI_3-DIN") (pintype "input"))
    )
    (net (code "6") (name "DI3") (class "Default")
      (node (ref "LED2") (pin "1-DOUT") (pinfunction "DO_1-DOUT") (pintype "output"))
      (node (ref "LED3") (pin "3-DIN") (pinfunction "DI_3-DIN") (pintype "input"))
    )
    (net (code "7") (name "DI4") (class "Default")
      (node (ref "LED3") (pin "1-DOUT") (pinfunction "DO_1-DOUT") (pintype "output"))
      (node (ref "LED4") (pin "3-DIN") (pinfunction "DI_3-DIN") (pintype "input"))
    )
    (net (code "8") (name "DI5") (class "Default")
      (node (ref "LED4") (pin "1-DOUT") (pinfunction "DO_1-DOUT") (pintype "output"))
      (node (ref "LED5") (pin "3-DIN") (pinfunction "DI_3-DIN") (pintype "input"))
    )
    (net (code "9") (name "DI6") (class "Default")
      (node (ref "LED5") (pin "1-DOUT") (pinfunction "DO_1-DOUT") (pintype "output"))
      (node (ref "LED6") (pin "3-DIN") (pinfunction "DI_3-DIN") (pintype "input"))
    )
    (net (code "10") (name "DI7") (class "Default")
      (node (ref "LED6") (pin "1-DOUT") (pinfunction "DO_1-DOUT") (pintype "output"))
      (node (ref "LED7") (pin "3-DIN") (pinfunction "DI_3-DIN") (pintype "input"))
    )
    (net (code "11") (name "DI8") (class "Default")
      (node (ref "LED7") (pin "1-DOUT") (pinfunction "DO_1-DOUT") (pintype "output"))
      (node (ref "LED8") (pin "3-DIN") (pinfunction "DI_3-DIN") (pintype "input"))
    )
    (net (code "12") (name "DI9") (class "Default")
      (node (ref "LED8") (pin "1-DOUT") (pinfunction "DO_1-DOUT") (pintype "output"))
      (node (ref "LED9") (pin "3-DIN") (pinfunction "DI_3-DIN") (pintype "input"))
    )
    (net (code "13") (name "DI10") (class "Default")
      (node (ref "LED10") (pin "3-DIN") (pinfunction "DI_3-DIN") (pintype "input"))
      (node (ref "LED9") (pin "1-DOUT") (pinfunction "DO_1-DOUT") (pintype "output"))
    )
    (net (code "14") (name "DI11") (class "Default")
      (node (ref "LED10") (pin "1-DOUT") (pinfunction "DO_1-DOUT") (pintype "output"))
      (node (ref "LED11") (pin "3-DIN") (pinfunction "DI_3-DIN") (pintype "input"))
    )
    (net (code "15") (name "DI12") (class "Default")
      (node (ref "LED11") (pin "1-DOUT") (pinfunction "DO_1-DOUT") (pintype "output"))
      (node (ref "LED12") (pin "3-DIN") (pinfunction "DI_3-DIN") (pintype "input"))
    )
    (net (code "16") (name "DI13") (class "Default")
      (node (ref "LED12") (pin "1-DOUT") (pinfunction "DO_1-DOUT") (pintype "output"))
      (node (ref "LED13") (pin "3-DIN") (pinfunction "DI_3-DIN") (pintype "input"))
    )
    (net (code "17") (name "DI14") (class "Default")
      (node (ref "LED13") (pin "1-DOUT") (pinfunction "DO_1-DOUT") (pintype "output"))
      (node (ref "LED14") (pin "3-DIN") (pinfunction "DI_3-DIN") (pintype "input"))
    )
    (net (code "18") (name "DI15") (class "Default")
      (node (ref "LED14") (pin "1-DOUT") (pinfunction "DO_1-DOUT") (pintype "output"))
      (node (ref "LED15") (pin "3-DIN") (pinfunction "DI_3-DIN") (pintype "input"))
    )
    (net (code "19") (name "DI16") (class "Default")
      (node (ref "LED15") (pin "1-DOUT") (pinfunction "DO_1-DOUT") (pintype "output"))
      (node (ref "LED16") (pin "3-DIN") (pinfunction "DI_3-DIN") (pintype "input"))
    )
    (net (code "20") (name "DI17") (class "Default")
      (node (ref "LED16") (pin "1-DOUT") (pinfunction "DO_1-DOUT") (pintype "output"))
      (node (ref "LED17") (pin "3-DIN") (pinfunction "DI_3-DIN") (pintype "input"))
    )
    (net (code "21") (name "DI18") (class "Default")
      (node (ref "LED17") (pin "1-DOUT") (pinfunction "DO_1-DOUT") (pintype "output"))
      (node (ref "LED18") (pin "3-DIN") (pinfunction "DI_3-DIN") (pintype "input"))
    )
    (net (code "22") (name "DI19") (class "Default")
      (node (ref "LED18") (pin "1-DOUT") (pinfunction "DO_1-DOUT") (pintype "output"))
      (node (ref "LED19") (pin "3-DIN") (pinfunction "DI_3-DIN") (pintype "input"))
    )
    (net (code "23") (name "DI20") (class "Default")
      (node (ref "LED19") (pin "1-DOUT") (pinfunction "DO_1-DOUT") (pintype "output"))
      (node (ref "LED20") (pin "3-DIN") (pinfunction "DI_3-DIN") (pintype "input"))
    )
    (net (code "24") (name "DI21") (class "Default")
      (node (ref "LED20") (pin "1-DOUT") (pinfunction "DO_1-DOUT") (pintype "output"))
      (node (ref "LED21") (pin "3-DIN") (pinfunction "DI_3-DIN") (pintype "input"))
    )
    (net (code "25") (name "DI22") (class "Default")
      (node (ref "LED21") (pin "1-DOUT") (pinfunction "DO_1-DOUT") (pintype "output"))
      (node (ref "LED22") (pin "3-DIN") (pinfunction "DI_3-DIN") (pintype "input"))
    )
    (net (code "26") (name "DI23") (class "Default")
      (node (ref "LED22") (pin "1-DOUT") (pinfunction "DO_1-DOUT") (pintype "output"))
      (node (ref "LED23") (pin "3-DIN") (pinfunction "DI_3-DIN") (pintype "input"))
    )
    (net (code "27") (name "DI24") (class "Default")
      (node (ref "LED23") (pin "1-DOUT") (pinfunction "DO_1-DOUT") (pintype "output"))
      (node (ref "LED24") (pin "3-DIN") (pinfunction "DI_3-DIN") (pintype "input"))
    )
    (net (code "28") (name "DI25") (class "Default")
      (node (ref "LED24") (pin "1-DOUT") (pinfunction "DO_1-DOUT") (pintype "output"))
      (node (ref "LED25") (pin "3-DIN") (pinfunction "DI_3-DIN") (pintype "input"))
    )
    (net (code "29") (name "DI26") (class "Default")
      (node (ref "LED25") (pin "1-DOUT") (pinfunction "DO_1-DOUT") (pintype "output"))
      (node (ref "LED26") (pin "3-DIN") (pinfunction "DI_3-DIN") (pintype "input"))
    )
    (net (code "30") (name "DI27") (class "Default")
      (node (ref "LED26") (pin "1-DOUT") (pinfunction "DO_1-DOUT") (pintype "output"))
      (node (ref "LED27") (pin "3-DIN") (pinfunction "DI_3-DIN") (pintype "input"))
    )
    (net (code "31") (name "DI28") (class "Default")
      (node (ref "LED27") (pin "1-DOUT") (pinfunction "DO_1-DOUT") (pintype "output"))
      (node (ref "LED28") (pin "3-DIN") (pinfunction "DI_3-DIN") (pintype "input"))
    )
    (net (code "32") (name "DI29") (class "Default")
      (node (ref "LED28") (pin "1-DOUT") (pinfunction "DO_1-DOUT") (pintype "output"))
      (node (ref "LED29") (pin "3-DIN") (pinfunction "DI_3-DIN") (pintype "input"))
    )
    (net (code "33") (name "DI30") (class "Default")
      (node (ref "LED29") (pin "1-DOUT") (pinfunction "DO_1-DOUT") (pintype "output"))
      (node (ref "LED30") (pin "3-DIN") (pinfunction "DI_3-DIN") (pintype "input"))
    )
    (net (code "34") (name "DI31") (class "Default")
      (node (ref "LED30") (pin "1-DOUT") (pinfunction "DO_1-DOUT") (pintype "output"))
      (node (ref "LED31") (pin "3-DIN") (pinfunction "DI_3-DIN") (pintype "input"))
    )
    (net (code "35") (name "DI32") (class "Default")
      (node (ref "LED31") (pin "1-DOUT") (pinfunction "DO_1-DOUT") (pintype "output"))
      (node (ref "LED32") (pin "3-DIN") (pinfunction "DI_3-DIN") (pintype "input"))
    )
    (net (code "36") (name "DI33") (class "Default")
      (node (ref "LED32") (pin "1-DOUT") (pinfunction "DO_1-DOUT") (pintype "output"))
      (node (ref "LED33") (pin "3-DIN") (pinfunction "DI_3-DIN") (pintype "input"))
    )
    (net (code "37") (name "DI34") (class "Default")
      (node (ref "LED33") (pin "1-DOUT") (pinfunction "DO_1-DOUT") (pintype "output"))
      (node (ref "LED34") (pin "3-DIN") (pinfunction "DI_3-DIN") (pintype "input"))
    )
    (net (code "38") (name "DI35") (class "Default")
      (node (ref "LED34") (pin "1-DOUT") (pinfunction "DO_1-DOUT") (pintype "output"))
      (node (ref "LED35") (pin "3-DIN") (pinfunction "DI_3-DIN") (pintype "input"))
    )
    (net (code "39") (name "DI36") (class "Default")
      (node (ref "LED35") (pin "1-DOUT") (pinfunction "DO_1-DOUT") (pintype "output"))
      (node (ref "LED36") (pin "3-DIN") (pinfunction "DI_3-DIN") (pintype "input"))
    )
    (net (code "40") (name "DI37") (class "Default")
      (node (ref "LED36") (pin "1-DOUT") (pinfunction "DO_1-DOUT") (pintype "output"))
      (node (ref "LED37") (pin "3-DIN") (pinfunction "DI_3-DIN") (pintype "input"))
    )
    (net (code "41") (name "DI38") (class "Default")
      (node (ref "LED37") (pin "1-DOUT") (pinfunction "DO_1-DOUT") (pintype "output"))
      (node (ref "LED38") (pin "3-DIN") (pinfunction "DI_3-DIN") (pintype "input"))
    )
    (net (code "42") (name "DI39") (class "Default")
      (node (ref "LED38") (pin "1-DOUT") (pinfunction "DO_1-DOUT") (pintype "output"))
      (node (ref "LED39") (pin "3-DIN") (pinfunction "DI_3-DIN") (pintype "input"))
    )
    (net (code "43") (name "DI40") (class "Default")
      (node (ref "LED39") (pin "1-DOUT") (pinfunction "DO_1-DOUT") (pintype "output"))
      (node (ref "LED40") (pin "3-DIN") (pinfunction "DI_3-DIN") (pintype "input"))
    )
    (net (code "44") (name "DI41") (class "Default")
      (node (ref "LED40") (pin "1-DOUT") (pinfunction "DO_1-DOUT") (pintype "output"))
      (node (ref "LED41") (pin "3-DIN") (pinfunction "DI_3-DIN") (pintype "input"))
    )
    (net (code "45") (name "DI42") (class "Default")
      (node (ref "LED41") (pin "1-DOUT") (pinfunction "DO_1-DOUT") (pintype "output"))
      (node (ref "LED42") (pin "3-DIN") (pinfunction "DI_3-DIN") (pintype "input"))
    )
    (net (code "46") (name "DI43") (class "Default")
      (node (ref "LED42") (pin "1-DOUT") (pinfunction "DO_1-DOUT") (pintype "output"))
      (node (ref "LED43") (pin "3-DIN") (pinfunction "DI_3-DIN") (pintype "input"))
    )
    (net (code "47") (name "DI44") (class "Default")
      (node (ref "LED43") (pin "1-DOUT") (pinfunction "DO_1-DOUT") (pintype "output"))
      (node (ref "LED44") (pin "3-DIN") (pinfunction "DI_3-DIN") (pintype "input"))
    )
    (net (code "48") (name "DI45") (class "Default")
      (node (ref "LED44") (pin "1-DOUT") (pinfunction "DO_1-DOUT") (pintype "output"))
      (node (ref "LED45") (pin "3-DIN") (pinfunction "DI_3-DIN") (pintype "input"))
    )
    (net (code "49") (name "DI46") (class "Default")
      (node (ref "LED45") (pin "1-DOUT") (pinfunction "DO_1-DOUT") (pintype "output"))
      (node (ref "LED46") (pin "3-DIN") (pinfunction "DI_3-DIN") (pintype "input"))
    )
    (net (code "50") (name "DI47") (class "Default")
      (node (ref "LED46") (pin "1-DOUT") (pinfunction "DO_1-DOUT") (pintype "output"))
      (node (ref "LED47") (pin "3-DIN") (pinfunction "DI_3-DIN") (pintype "input"))
    )
    (net (code "51") (name "DI48") (class "Default")
      (node (ref "LED47") (pin "1-DOUT") (pinfunction "DO_1-DOUT") (pintype "output"))
      (node (ref "LED48") (pin "3-DIN") (pinfunction "DI_3-DIN") (pintype "input"))
    )
    (net (code "52") (name "DI49") (class "Default")
      (node (ref "LED48") (pin "1-DOUT") (pinfunction "DO_1-DOUT") (pintype "output"))
      (node (ref "LED49") (pin "3-DIN") (pinfunction "DI_3-DIN") (pintype "input"))
    )
    (net (code "53") (name "DI50") (class "Default")
      (node (ref "LED49") (pin "1-DOUT") (pinfunction "DO_1-DOUT") (pintype "output"))
      (node (ref "LED50") (pin "3-DIN") (pinfunction "DI_3-DIN") (pintype "input"))
    )
    (net (code "54") (name "DI51") (class "Default")
      (node (ref "LED50") (pin "1-DOUT") (pinfunction "DO_1-DOUT") (pintype "output"))
      (node (ref "LED51") (pin "3-DIN") (pinfunction "DI_3-DIN") (pintype "input"))
    )
    (net (code "55") (name "DI52") (class "Default")
      (node (ref "LED51") (pin "1-DOUT") (pinfunction "DO_1-DOUT") (pintype "output"))
      (node (ref "LED52") (pin "3-DIN") (pinfunction "DI_3-DIN") (pintype "input"))
    )
    (net (code "56") (name "DI53") (class "Default")
      (node (ref "LED52") (pin "1-DOUT") (pinfunction "DO_1-DOUT") (pintype "output"))
      (node (ref "LED53") (pin "3-DIN") (pinfunction "DI_3-DIN") (pintype "input"))
    )
    (net (code "57") (name "DI54") (class "Default")
      (node (ref "LED53") (pin "1-DOUT") (pinfunction "DO_1-DOUT") (pintype "output"))
      (node (ref "LED54") (pin "3-DIN") (pinfunction "DI_3-DIN") (pintype "input"))
    )
    (net (code "58") (name "DI55") (class "Default")
      (node (ref "LED54") (pin "1-DOUT") (pinfunction "DO_1-DOUT") (pintype "output"))
      (node (ref "LED55") (pin "3-DIN") (pinfunction "DI_3-DIN") (pintype "input"))
    )
    (net (code "59") (name "DI56") (class "Default")
      (node (ref "LED55") (pin "1-DOUT") (pinfunction "DO_1-DOUT") (pintype "output"))
      (node (ref "LED56") (pin "3-DIN") (pinfunction "DI_3-DIN") (pintype "input"))
    )
    (net (code "60") (name "DI57") (class "Default")
      (node (ref "LED56") (pin "1-DOUT") (pinfunction "DO_1-DOUT") (pintype "output"))
      (node (ref "LED57") (pin "3-DIN") (pinfunction "DI_3-DIN") (pintype "input"))
    )
    (net (code "61") (name "DI58") (class "Default")
      (node (ref "LED57") (pin "1-DOUT") (pinfunction "DO_1-DOUT") (pintype "output"))
      (node (ref "LED58") (pin "3-DIN") (pinfunction "DI_3-DIN") (pintype "input"))
    )
    (net (code "62") (name "DI59") (class "Default")
      (node (ref "LED58") (pin "1-DOUT") (pinfunction "DO_1-DOUT") (pintype "output"))
      (node (ref "LED59") (pin "3-DIN") (pinfunction "DI_3-DIN") (pintype "input"))
    )
    (net (code "63") (name "DI60") (class "Default")
      (node (ref "LED59") (pin "1-DOUT") (pinfunction "DO_1-DOUT") (pintype "output"))
      (node (ref "LED60") (pin "3-DIN") (pinfunction "DI_3-DIN") (pintype "input"))
    )
    (net (code "64") (name "DI61") (class "Default")
      (node (ref "LED60") (pin "1-DOUT") (pinfunction "DO_1-DOUT") (pintype "output"))
      (node (ref "LED61") (pin "3-DIN") (pinfunction "DI_3-DIN") (pintype "input"))
    )
    (net (code "65") (name "DI62") (class "Default")
      (node (ref "LED61") (pin "1-DOUT") (pinfunction "DO_1-DOUT") (pintype "output"))
      (node (ref "LED62") (pin "3-DIN") (pinfunction "DI_3-DIN") (pintype "input"))
    )
    (net (code "66") (name "DI63") (class "Default")
      (node (ref "LED62") (pin "1-DOUT") (pinfunction "DO_1-DOUT") (pintype "output"))
      (node (ref "LED63") (pin "3-DIN") (pinfunction "DI_3-DIN") (pintype "input"))
    )
    (net (code "67") (name "DI64") (class "Default")
      (node (ref "LED63") (pin "1-DOUT") (pinfunction "DO_1-DOUT") (pintype "output"))
      (node (ref "LED64") (pin "3-DIN") (pinfunction "DI_3-DIN") (pintype "input"))
    )
    (net (code "68") (name "DI65") (class "Default")
      (node (ref "LED64") (pin "1-DOUT") (pinfunction "DO_1-DOUT") (pintype "output"))
      (node (ref "LED65") (pin "3-DIN") (pinfunction "DI_3-DIN") (pintype "input"))
    )
    (net (code "69") (name "DI66") (class "Default")
      (node (ref "LED65") (pin "1-DOUT") (pinfunction "DO_1-DOUT") (pintype "output"))
      (node (ref "LED66") (pin "3-DIN") (pinfunction "DI_3-DIN") (pintype "input"))
    )
    (net (code "70") (name "DI67") (class "Default")
      (node (ref "LED66") (pin "1-DOUT") (pinfunction "DO_1-DOUT") (pintype "output"))
      (node (ref "LED67") (pin "3-DIN") (pinfunction "DI_3-DIN") (pintype "input"))
    )
    (net (code "71") (name "DI68") (class "Default")
      (node (ref "LED67") (pin "1-DOUT") (pinfunction "DO_1-DOUT") (pintype "output"))
      (node (ref "LED68") (pin "3-DIN") (pinfunction "DI_3-DIN") (pintype "input"))
    )
    (net (code "72") (name "DI69") (class "Default")
      (node (ref "LED68") (pin "1-DOUT") (pinfunction "DO_1-DOUT") (pintype "output"))
      (node (ref "LED69") (pin "3-DIN") (pinfunction "DI_3-DIN") (pintype "input"))
    )
    (net (code "73") (name "DI70") (class "Default")
      (node (ref "LED69") (pin "1-DOUT") (pinfunction "DO_1-DOUT") (pintype "output"))
      (node (ref "LED70") (pin "3-DIN") (pinfunction "DI_3-DIN") (pintype "input"))
    )
    (net (code "74") (name "DI71") (class "Default")
      (node (ref "LED70") (pin "1-DOUT") (pinfunction "DO_1-DOUT") (pintype "output"))
      (node (ref "LED71") (pin "3-DIN") (pinfunction "DI_3-DIN") (pintype "input"))
    )
    (net (code "75") (name "DI72") (class "Default")
      (node (ref "LED71") (pin "1-DOUT") (pinfunction "DO_1-DOUT") (pintype "output"))
      (node (ref "LED72") (pin "3-DIN") (pinfunction "DI_3-DIN") (pintype "input"))
    )
    (net (code "76") (name "DI73") (class "Default")
      (node (ref "LED72") (pin "1-DOUT") (pinfunction "DO_1-DOUT") (pintype "output"))
      (node (ref "LED73") (pin "3-DIN") (pinfunction "DI_3-DIN") (pintype "input"))
    )
    (net (code "77") (name "DI74") (class "Default")
      (node (ref "LED73") (pin "1-DOUT") (pinfunction "DO_1-DOUT") (pintype "output"))
      (node (ref "LED74") (pin "3-DIN") (pinfunction "DI_3-DIN") (pintype "input"))
    )
    (net (code "78") (name "DI75") (class "Default")
      (node (ref "LED74") (pin "1-DOUT") (pinfunction "DO_1-DOUT") (pintype "output"))
      (node (ref "LED75") (pin "3-DIN") (pinfunction "DI_3-DIN") (pintype "input"))
    )
    (net (code "79") (name "DI76") (class "Default")
      (node (ref "LED75") (pin "1-DOUT") (pinfunction "DO_1-DOUT") (pintype "output"))
      (node (ref "LED76") (pin "3-DIN") (pinfunction "DI_3-DIN") (pintype "input"))
    )
    (net (code "80") (name "DI77") (class "Default")
      (node (ref "LED76") (pin "1-DOUT") (pinfunction "DO_1-DOUT") (pintype "output"))
      (node (ref "LED77") (pin "3-DIN") (pinfunction "DI_3-DIN") (pintype "input"))
    )
    (net (code "81") (name "DI78") (class "Default")
      (node (ref "LED77") (pin "1-DOUT") (pinfunction "DO_1-DOUT") (pintype "output"))
      (node (ref "LED78") (pin "3-DIN") (pinfunction "DI_3-DIN") (pintype "input"))
    )
    (net (code "82") (name "DI79") (class "Default")
      (node (ref "LED78") (pin "1-DOUT") (pinfunction "DO_1-DOUT") (pintype "output"))
      (node (ref "LED79") (pin "3-DIN") (pinfunction "DI_3-DIN") (pintype "input"))
    )
    (net (code "83") (name "DI80") (class "Default")
      (node (ref "LED79") (pin "1-DOUT") (pinfunction "DO_1-DOUT") (pintype "output"))
      (node (ref "LED80") (pin "3-DIN") (pinfunction "DI_3-DIN") (pintype "input"))
    )
    (net (code "84") (name "DI81") (class "Default")
      (node (ref "LED80") (pin "1-DOUT") (pinfunction "DO_1-DOUT") (pintype "output"))
      (node (ref "LED81") (pin "3-DIN") (pinfunction "DI_3-DIN") (pintype "input"))
    )
    (net (code "85") (name "DI82") (class "Default")
      (node (ref "LED81") (pin "1-DOUT") (pinfunction "DO_1-DOUT") (pintype "output"))
      (node (ref "LED82") (pin "3-DIN") (pinfunction "DI_3-DIN") (pintype "input"))
    )
    (net (code "86") (name "DI83") (class "Default")
      (node (ref "LED82") (pin "1-DOUT") (pinfunction "DO_1-DOUT") (pintype "output"))
      (node (ref "LED83") (pin "3-DIN") (pinfunction "DI_3-DIN") (pintype "input"))
    )
    (net (code "87") (name "DI84") (class "Default")
      (node (ref "LED83") (pin "1-DOUT") (pinfunction "DO_1-DOUT") (pintype "output"))
      (node (ref "LED84") (pin "3-DIN") (pinfunction "DI_3-DIN") (pintype "input"))
    )
    (net (code "88") (name "DI85") (class "Default")
      (node (ref "LED84") (pin "1-DOUT") (pinfunction "DO_1-DOUT") (pintype "output"))
      (node (ref "LED85") (pin "3-DIN") (pinfunction "DI_3-DIN") (pintype "input"))
    )
    (net (code "89") (name "DI86") (class "Default")
      (node (ref "LED85") (pin "1-DOUT") (pinfunction "DO_1-DOUT") (pintype "output"))
      (node (ref "LED86") (pin "3-DIN") (pinfunction "DI_3-DIN") (pintype "input"))
    )
    (net (code "90") (name "DI87") (class "Default")
      (node (ref "LED86") (pin "1-DOUT") (pinfunction "DO_1-DOUT") (pintype "output"))
      (node (ref "LED87") (pin "3-DIN") (pinfunction "DI_3-DIN") (pintype "input"))
    )
    (net (code "91") (name "DI88") (class "Default")
      (node (ref "LED87") (pin "1-DOUT") (pinfunction "DO_1-DOUT") (pintype "output"))
      (node (ref "LED88") (pin "3-DIN") (pinfunction "DI_3-DIN") (pintype "input"))
    )
    (net (code "92") (name "DI89") (class "Default")
      (node (ref "LED88") (pin "1-DOUT") (pinfunction "DO_1-DOUT") (pintype "output"))
      (node (ref "LED89") (pin "3-DIN") (pinfunction "DI_3-DIN") (pintype "input"))
    )
    (net (code "93") (name "DI90") (class "Default")
      (node (ref "LED89") (pin "1-DOUT") (pinfunction "DO_1-DOUT") (pintype "output"))
      (node (ref "LED90") (pin "3-DIN") (pinfunction "DI_3-DIN") (pintype "input"))
    )
    (net (code "94") (name "DI91") (class "Default")
      (node (ref "LED90") (pin "1-DOUT") (pinfunction "DO_1-DOUT") (pintype "output"))
      (node (ref "LED91") (pin "3-DIN") (pinfunction "DI_3-DIN") (pintype "input"))
    )
    (net (code "95") (name "DI92") (class "Default")
      (node (ref "LED91") (pin "1-DOUT") (pinfunction "DO_1-DOUT") (pintype "output"))
      (node (ref "LED92") (pin "3-DIN") (pinfunction "DI_3-DIN") (pintype "input"))
    )
    (net (code "96") (name "DI93") (class "Default")
      (node (ref "LED92") (pin "1-DOUT") (pinfunction "DO_1-DOUT") (pintype "output"))
      (node (ref "LED93") (pin "3-DIN") (pinfunction "DI_3-DIN") (pintype "input"))
    )
    (net (code "97") (name "DI94") (class "Default")
      (node (ref "LED93") (pin "1-DOUT") (pinfunction "DO_1-DOUT") (pintype "output"))
      (node (ref "LED94") (pin "3-DIN") (pinfunction "DI_3-DIN") (pintype "input"))
    )
    (net (code "98") (name "DI95") (class "Default")
      (node (ref "LED94") (pin "1-DOUT") (pinfunction "DO_1-DOUT") (pintype "output"))
      (node (ref "LED95") (pin "3-DIN") (pinfunction "DI_3-DIN") (pintype "input"))
    )
    (net (code "99") (name "DI96") (class "Default")
      (node (ref "LED95") (pin "1-DOUT") (pinfunction "DO_1-DOUT") (pintype "output"))
      (node (ref "LED96") (pin "3-DIN") (pinfunction "DI_3-DIN") (pintype "input"))
    )
    (net (code "100") (name "DI97") (class "Default")
      (node (ref "LED96") (pin "1-DOUT") (pinfunction "DO_1-DOUT") (pintype "output"))
      (node (ref "LED97") (pin "3-DIN") (pinfunction "DI_3-DIN") (pintype "input"))
    )
    (net (code "101") (name "DI98") (class "Default")
      (node (ref "LED97") (pin "1-DOUT") (pinfunction "DO_1-DOUT") (pintype "output"))
      (node (ref "LED98") (pin "3-DIN") (pinfunction "DI_3-DIN") (pintype "input"))
    )
    (net (code "102") (name "DI99") (class "Default")
      (node (ref "LED98") (pin "1-DOUT") (pinfunction "DO_1-DOUT") (pintype "output"))
      (node (ref "LED99") (pin "3-DIN") (pinfunction "DI_3-DIN") (pintype "input"))
    )
    (net (code "103") (name "DI100") (class "Default")
      (node (ref "LED100") (pin "3-DIN") (pinfunction "DI_3-DIN") (pintype "input"))
      (node (ref "LED99") (pin "1-DOUT") (pinfunction "DO_1-DOUT") (pintype "output"))
    )
    (net (code "104") (name "DI101") (class "Default")
      (node (ref "LED100") (pin "1-DOUT") (pinfunction "DO_1-DOUT") (pintype "output"))
      (node (ref "LED101") (pin "3-DIN") (pinfunction "DI_3-DIN") (pintype "input"))
    )
    (net (code "105") (name "DI102") (class "Default")
      (node (ref "LED101") (pin "1-DOUT") (pinfunction "DO_1-DOUT") (pintype "output"))
      (node (ref "LED102") (pin "3-DIN") (pinfunction "DI_3-DIN") (pintype "input"))
    )
    (net (code "106") (name "DI103") (class "Default")
      (node (ref "LED102") (pin "1-DOUT") (pinfunction "DO_1-DOUT") (pintype "output"))
      (node (ref "LED103") (pin "3-DIN") (pinfunction "DI_3-DIN") (pintype "input"))
    )
    (net (code "107") (name "DI104") (class "Default")
      (node (ref "LED103") (pin "1-DOUT") (pinfunction "DO_1-DOUT") (pintype "output"))
      (node (ref "LED104") (pin "3-DIN") (pinfunction "DI_3-DIN") (pintype "input"))
    )
    (net (code "108") (name "DI105") (class "Default")
      (node (ref "LED104") (pin "1-DOUT") (pinfunction "DO_1-DOUT") (pintype "output"))
      (node (ref "LED105") (pin "3-DIN") (pinfunction "DI_3-DIN") (pintype "input"))
    )
    (net (code "109") (name "DO") (class "Default")
      (node (ref "JP1") (pin "1") (pinfunction "1_1") (pintype "passive"))
      (node (ref "LED105") (pin "1-DOUT") (pinfunction "DO_1-DOUT") (pintype "output"))
    )
    (net (code "110") (name "GND") (class "Default")
      (node (ref "C1") (pin "1") (pinfunction "1_1") (pintype "passive"))
      (node (ref "C2") (pin "1") (pinfunction "1_1") (pintype "passive"))
      (node (ref "C3") (pin "P$2") (pinfunction "2_P$2") (pintype "passive"))
      (node (ref "C4") (pin "P$2") (pinfunction "2_P$2") (pintype "passive"))
      (node (ref "C5") (pin "2") (pinfunction "2_2") (pintype "passive"))
      (node (ref "C6") (pin "2") (pinfunction "2_2") (pintype "passive"))
      (node (ref "C7") (pin "2") (pinfunction "2_2") (pintype "passive"))
      (node (ref "C8") (pin "2") (pinfunction "2_2") (pintype "passive"))
      (node (ref "C9") (pin "2") (pinfunction "2_2") (pintype "passive"))
      (node (ref "CON1") (pin "A1") (pinfunction "GND_A1") (pintype "passive"))
      (node (ref "CON1") (pin "A12") (pinfunction "GND1_A12") (pintype "passive"))
      (node (ref "CON1") (pin "B1") (pinfunction "GND3_B1") (pintype "passive"))
      (node (ref "CON1") (pin "B12") (pinfunction "GND2_B12") (pintype "passive"))
      (node (ref "CON1") (pin "P$1") (pinfunction "SHIELD_P$1") (pintype "passive"))
      (node (ref "CON1") (pin "P$2") (pinfunction "SHIELD_P$2") (pintype "passive"))
      (node (ref "CON1") (pin "P$3") (pinfunction "SHIELD_P$3") (pintype "passive"))
      (node (ref "CON1") (pin "P$4") (pinfunction "SHIELD_P$4") (pintype "passive"))
      (node (ref "D1") (pin "1") (pinfunction "-_1") (pintype "passive"))
      (node (ref "D3") (pin "2") (pinfunction "GND_2") (pintype "passive"))
      (node (ref "LED1") (pin "4-GND") (pinfunction "GND_4-GND") (pintype "power_in"))
      (node (ref "LED10") (pin "4-GND") (pinfunction "GND_4-GND") (pintype "power_in"))
      (node (ref "LED100") (pin "4-GND") (pinfunction "GND_4-GND") (pintype "power_in"))
      (node (ref "LED101") (pin "4-GND") (pinfunction "GND_4-GND") (pintype "power_in"))
      (node (ref "LED102") (pin "4-GND") (pinfunction "GND_4-GND") (pintype "power_in"))
      (node (ref "LED103") (pin "4-GND") (pinfunction "GND_4-GND") (pintype "power_in"))
      (node (ref "LED104") (pin "4-GND") (pinfunction "GND_4-GND") (pintype "power_in"))
      (node (ref "LED105") (pin "4-GND") (pinfunction "GND_4-GND") (pintype "power_in"))
      (node (ref "LED11") (pin "4-GND") (pinfunction "GND_4-GND") (pintype "power_in"))
      (node (ref "LED12") (pin "4-GND") (pinfunction "GND_4-GND") (pintype "power_in"))
      (node (ref "LED13") (pin "4-GND") (pinfunction "GND_4-GND") (pintype "power_in"))
      (node (ref "LED14") (pin "4-GND") (pinfunction "GND_4-GND") (pintype "power_in"))
      (node (ref "LED15") (pin "4-GND") (pinfunction "GND_4-GND") (pintype "power_in"))
      (node (ref "LED16") (pin "4-GND") (pinfunction "GND_4-GND") (pintype "power_in"))
      (node (ref "LED17") (pin "4-GND") (pinfunction "GND_4-GND") (pintype "power_in"))
      (node (ref "LED18") (pin "4-GND") (pinfunction "GND_4-GND") (pintype "power_in"))
      (node (ref "LED19") (pin "4-GND") (pinfunction "GND_4-GND") (pintype "power_in"))
      (node (ref "LED2") (pin "4-GND") (pinfunction "GND_4-GND") (pintype "power_in"))
      (node (ref "LED20") (pin "4-GND") (pinfunction "GND_4-GND") (pintype "power_in"))
      (node (ref "LED21") (pin "4-GND") (pinfunction "GND_4-GND") (pintype "power_in"))
      (node (ref "LED22") (pin "4-GND") (pinfunction "GND_4-GND") (pintype "power_in"))
      (node (ref "LED23") (pin "4-GND") (pinfunction "GND_4-GND") (pintype "power_in"))
      (node (ref "LED24") (pin "4-GND") (pinfunction "GND_4-GND") (pintype "power_in"))
      (node (ref "LED25") (pin "4-GND") (pinfunction "GND_4-GND") (pintype "power_in"))
      (node (ref "LED26") (pin "4-GND") (pinfunction "GND_4-GND") (pintype "power_in"))
      (node (ref "LED27") (pin "4-GND") (pinfunction "GND_4-GND") (pintype "power_in"))
      (node (ref "LED28") (pin "4-GND") (pinfunction "GND_4-GND") (pintype "power_in"))
      (node (ref "LED29") (pin "4-GND") (pinfunction "GND_4-GND") (pintype "power_in"))
      (node (ref "LED3") (pin "4-GND") (pinfunction "GND_4-GND") (pintype "power_in"))
      (node (ref "LED30") (pin "4-GND") (pinfunction "GND_4-GND") (pintype "power_in"))
      (node (ref "LED31") (pin "4-GND") (pinfunction "GND_4-GND") (pintype "power_in"))
      (node (ref "LED32") (pin "4-GND") (pinfunction "GND_4-GND") (pintype "power_in"))
      (node (ref "LED33") (pin "4-GND") (pinfunction "GND_4-GND") (pintype "power_in"))
      (node (ref "LED34") (pin "4-GND") (pinfunction "GND_4-GND") (pintype "power_in"))
      (node (ref "LED35") (pin "4-GND") (pinfunction "GND_4-GND") (pintype "power_in"))
      (node (ref "LED36") (pin "4-GND") (pinfunction "GND_4-GND") (pintype "power_in"))
      (node (ref "LED37") (pin "4-GND") (pinfunction "GND_4-GND") (pintype "power_in"))
      (node (ref "LED38") (pin "4-GND") (pinfunction "GND_4-GND") (pintype "power_in"))
      (node (ref "LED39") (pin "4-GND") (pinfunction "GND_4-GND") (pintype "power_in"))
      (node (ref "LED4") (pin "4-GND") (pinfunction "GND_4-GND") (pintype "power_in"))
      (node (ref "LED40") (pin "4-GND") (pinfunction "GND_4-GND") (pintype "power_in"))
      (node (ref "LED41") (pin "4-GND") (pinfunction "GND_4-GND") (pintype "power_in"))
      (node (ref "LED42") (pin "4-GND") (pinfunction "GND_4-GND") (pintype "power_in"))
      (node (ref "LED43") (pin "4-GND") (pinfunction "GND_4-GND") (pintype "power_in"))
      (node (ref "LED44") (pin "4-GND") (pinfunction "GND_4-GND") (pintype "power_in"))
      (node (ref "LED45") (pin "4-GND") (pinfunction "GND_4-GND") (pintype "power_in"))
      (node (ref "LED46") (pin "4-GND") (pinfunction "GND_4-GND") (pintype "power_in"))
      (node (ref "LED47") (pin "4-GND") (pinfunction "GND_4-GND") (pintype "power_in"))
      (node (ref "LED48") (pin "4-GND") (pinfunction "GND_4-GND") (pintype "power_in"))
      (node (ref "LED49") (pin "4-GND") (pinfunction "GND_4-GND") (pintype "power_in"))
      (node (ref "LED5") (pin "4-GND") (pinfunction "GND_4-GND") (pintype "power_in"))
      (node (ref "LED50") (pin "4-GND") (pinfunction "GND_4-GND") (pintype "power_in"))
      (node (ref "LED51") (pin "4-GND") (pinfunction "GND_4-GND") (pintype "power_in"))
      (node (ref "LED52") (pin "4-GND") (pinfunction "GND_4-GND") (pintype "power_in"))
      (node (ref "LED53") (pin "4-GND") (pinfunction "GND_4-GND") (pintype "power_in"))
      (node (ref "LED54") (pin "4-GND") (pinfunction "GND_4-GND") (pintype "power_in"))
      (node (ref "LED55") (pin "4-GND") (pinfunction "GND_4-GND") (pintype "power_in"))
      (node (ref "LED56") (pin "4-GND") (pinfunction "GND_4-GND") (pintype "power_in"))
      (node (ref "LED57") (pin "4-GND") (pinfunction "GND_4-GND") (pintype "power_in"))
      (node (ref "LED58") (pin "4-GND") (pinfunction "GND_4-GND") (pintype "power_in"))
      (node (ref "LED59") (pin "4-GND") (pinfunction "GND_4-GND") (pintype "power_in"))
      (node (ref "LED6") (pin "4-GND") (pinfunction "GND_4-GND") (pintype "power_in"))
      (node (ref "LED60") (pin "4-GND") (pinfunction "GND_4-GND") (pintype "power_in"))
      (node (ref "LED61") (pin "4-GND") (pinfunction "GND_4-GND") (pintype "power_in"))
      (node (ref "LED62") (pin "4-GND") (pinfunction "GND_4-GND") (pintype "power_in"))
      (node (ref "LED63") (pin "4-GND") (pinfunction "GND_4-GND") (pintype "power_in"))
      (node (ref "LED64") (pin "4-GND") (pinfunction "GND_4-GND") (pintype "power_in"))
      (node (ref "LED65") (pin "4-GND") (pinfunction "GND_4-GND") (pintype "power_in"))
      (node (ref "LED66") (pin "4-GND") (pinfunction "GND_4-GND") (pintype "power_in"))
      (node (ref "LED67") (pin "4-GND") (pinfunction "GND_4-GND") (pintype "power_in"))
      (node (ref "LED68") (pin "4-GND") (pinfunction "GND_4-GND") (pintype "power_in"))
      (node (ref "LED69") (pin "4-GND") (pinfunction "GND_4-GND") (pintype "power_in"))
      (node (ref "LED7") (pin "4-GND") (pinfunction "GND_4-GND") (pintype "power_in"))
      (node (ref "LED70") (pin "4-GND") (pinfunction "GND_4-GND") (pintype "power_in"))
      (node (ref "LED71") (pin "4-GND") (pinfunction "GND_4-GND") (pintype "power_in"))
      (node (ref "LED72") (pin "4-GND") (pinfunction "GND_4-GND") (pintype "power_in"))
      (node (ref "LED73") (pin "4-GND") (pinfunction "GND_4-GND") (pintype "power_in"))
      (node (ref "LED74") (pin "4-GND") (pinfunction "GND_4-GND") (pintype "power_in"))
      (node (ref "LED75") (pin "4-GND") (pinfunction "GND_4-GND") (pintype "power_in"))
      (node (ref "LED76") (pin "4-GND") (pinfunction "GND_4-GND") (pintype "power_in"))
      (node (ref "LED77") (pin "4-GND") (pinfunction "GND_4-GND") (pintype "power_in"))
      (node (ref "LED78") (pin "4-GND") (pinfunction "GND_4-GND") (pintype "power_in"))
      (node (ref "LED79") (pin "4-GND") (pinfunction "GND_4-GND") (pintype "power_in"))
      (node (ref "LED8") (pin "4-GND") (pinfunction "GND_4-GND") (pintype "power_in"))
      (node (ref "LED80") (pin "4-GND") (pinfunction "GND_4-GND") (pintype "power_in"))
      (node (ref "LED81") (pin "4-GND") (pinfunction "GND_4-GND") (pintype "power_in"))
      (node (ref "LED82") (pin "4-GND") (pinfunction "GND_4-GND") (pintype "power_in"))
      (node (ref "LED83") (pin "4-GND") (pinfunction "GND_4-GND") (pintype "power_in"))
      (node (ref "LED84") (pin "4-GND") (pinfunction "GND_4-GND") (pintype "power_in"))
      (node (ref "LED85") (pin "4-GND") (pinfunction "GND_4-GND") (pintype "power_in"))
      (node (ref "LED86") (pin "4-GND") (pinfunction "GND_4-GND") (pintype "power_in"))
      (node (ref "LED87") (pin "4-GND") (pinfunction "GND_4-GND") (pintype "power_in"))
      (node (ref "LED88") (pin "4-GND") (pinfunction "GND_4-GND") (pintype "power_in"))
      (node (ref "LED89") (pin "4-GND") (pinfunction "GND_4-GND") (pintype "power_in"))
      (node (ref "LED9") (pin "4-GND") (pinfunction "GND_4-GND") (pintype "power_in"))
      (node (ref "LED90") (pin "4-GND") (pinfunction "GND_4-GND") (pintype "power_in"))
      (node (ref "LED91") (pin "4-GND") (pinfunction "GND_4-GND") (pintype "power_in"))
      (node (ref "LED92") (pin "4-GND") (pinfunction "GND_4-GND") (pintype "power_in"))
      (node (ref "LED93") (pin "4-GND") (pinfunction "GND_4-GND") (pintype "power_in"))
      (node (ref "LED94") (pin "4-GND") (pinfunction "GND_4-GND") (pintype "power_in"))
      (node (ref "LED95") (pin "4-GND") (pinfunction "GND_4-GND") (pintype "power_in"))
      (node (ref "LED96") (pin "4-GND") (pinfunction "GND_4-GND") (pintype "power_in"))
      (node (ref "LED97") (pin "4-GND") (pinfunction "GND_4-GND") (pintype "power_in"))
      (node (ref "LED98") (pin "4-GND") (pinfunction "GND_4-GND") (pintype "power_in"))
      (node (ref "LED99") (pin "4-GND") (pinfunction "GND_4-GND") (pintype "power_in"))
      (node (ref "MS1") (pin "4") (pinfunction "GND_4") (pintype "power_in"))
      (node (ref "R1") (pin "1") (pinfunction "1_1") (pintype "passive"))
      (node (ref "R2") (pin "2") (pinfunction "2_2") (pintype "passive"))
      (node (ref "S1") (pin "3") (pinfunction "3_3") (pintype "passive"))
      (node (ref "S1") (pin "4") (pinfunction "4_4") (pintype "passive"))
      (node (ref "S1") (pin "5") (pinfunction "4_5") (pintype "passive"))
      (node (ref "S1") (pin "6") (pinfunction "3_6") (pintype "passive"))
      (node (ref "S2") (pin "3") (pinfunction "3_3") (pintype "passive"))
      (node (ref "S2") (pin "4") (pinfunction "4_4") (pintype "passive"))
      (node (ref "S2") (pin "5") (pinfunction "4_5") (pintype "passive"))
      (node (ref "S2") (pin "6") (pinfunction "3_6") (pintype "passive"))
      (node (ref "ST2") (pin "1") (pinfunction "1_1") (pintype "bidirectional"))
      (node (ref "U$1") (pin "2") (pinfunction "GND_2") (pintype "input"))
    )
    (net (code "111") (name "Net-(CON1-CC1)") (class "Default")
      (node (ref "CON1") (pin "A5") (pinfunction "CC1_A5") (pintype "passive"))
      (node (ref "R1") (pin "2") (pinfunction "2_2") (pintype "passive"))
    )
    (net (code "112") (name "Net-(CON1-CC2)") (class "Default")
      (node (ref "CON1") (pin "B5") (pinfunction "CC2_B5") (pintype "passive"))
      (node (ref "R2") (pin "1") (pinfunction "1_1") (pintype "passive"))
    )
    (net (code "113") (name "Net-(D1-+)") (class "Default")
      (node (ref "D1") (pin "2") (pinfunction "+_2") (pintype "passive"))
      (node (ref "R6") (pin "1") (pinfunction "1_1") (pintype "passive"))
    )
    (net (code "114") (name "Net-(MS1-GPIO6)") (class "Default")
      (node (ref "MS1") (pin "20") (pinfunction "GPIO6_20") (pintype "bidirectional"))
      (node (ref "R9") (pin "1") (pinfunction "1_1") (pintype "passive"))
    )
    (net (code "115") (name "Net-(MS1-GPIO12)") (class "Default")
      (node (ref "MS1") (pin "24") (pinfunction "GPIO12_24") (pintype "bidirectional"))
      (node (ref "R4") (pin "1") (pinfunction "1_1") (pintype "passive"))
    )
    (net (code "116") (name "Net-(MS1-GPIOMOSI)") (class "Default")
      (node (ref "MS1") (pin "12") (pinfunction "GPIOMOSI_12") (pintype "bidirectional"))
      (node (ref "R10") (pin "1") (pinfunction "1_1") (pintype "passive"))
    )
    (net (code "117") (name "Net-(MS1-USB)") (class "Default")
      (node (ref "MS1") (pin "26") (pinfunction "USB_26") (pintype "power_in"))
      (node (ref "R8") (pin "1") (pinfunction "1_1") (pintype "passive"))
    )
    (net (code "118") (name "Net-(U$1-A)") (class "Default")
      (node (ref "R5") (pin "1") (pinfunction "1_1") (pintype "passive"))
      (node (ref "U$1") (pin "3") (pinfunction "A_3") (pintype "open_collector"))
    )
    (net (code "119") (name "Net-(U$1-B)") (class "Default")
      (node (ref "R3") (pin "1") (pinfunction "1_1") (pintype "passive"))
      (node (ref "R7") (pin "1") (pinfunction "1_1") (pintype "passive"))
      (node (ref "U$1") (pin "4") (pinfunction "B_4") (pintype "power_in"))
    )
    (net (code "120") (name "PROG") (class "Default")
      (node (ref "MS1") (pin "19") (pinfunction "GPIO5_19") (pintype "bidirectional"))
      (node (ref "S2") (pin "1") (pinfunction "1_1") (pintype "passive"))
      (node (ref "S2") (pin "2") (pinfunction "2_2") (pintype "passive"))
      (node (ref "S2") (pin "7") (pinfunction "1_7") (pintype "passive"))
      (node (ref "S2") (pin "8") (pinfunction "2_8") (pintype "passive"))
    )
    (net (code "121") (name "VBAT") (class "Default")
      (node (ref "D2") (pin "A") (pinfunction "A_A") (pintype "passive"))
      (node (ref "MS1") (pin "28") (pinfunction "VBAT_28") (pintype "power_in"))
    )
    (net (code "122") (name "VDD") (class "Default")
      (node (ref "C2") (pin "2") (pinfunction "2_2") (pintype "passive"))
      (node (ref "C7") (pin "1") (pinfunction "1_1") (pintype "passive"))
      (node (ref "C8") (pin "1") (pinfunction "1_1") (pintype "passive"))
      (node (ref "C9") (pin "1") (pinfunction "1_1") (pintype "passive"))
      (node (ref "F1") (pin "2") (pinfunction "2_2") (pintype "passive"))
      (node (ref "F2") (pin "2") (pinfunction "2_2") (pintype "passive"))
      (node (ref "LED1") (pin "2-VDD") (pinfunction "VDD_2-VDD") (pintype "power_in"))
      (node (ref "LED10") (pin "2-VDD") (pinfunction "VDD_2-VDD") (pintype "power_in"))
      (node (ref "LED100") (pin "2-VDD") (pinfunction "VDD_2-VDD") (pintype "power_in"))
      (node (ref "LED101") (pin "2-VDD") (pinfunction "VDD_2-VDD") (pintype "power_in"))
      (node (ref "LED102") (pin "2-VDD") (pinfunction "VDD_2-VDD") (pintype "power_in"))
      (node (ref "LED103") (pin "2-VDD") (pinfunction "VDD_2-VDD") (pintype "power_in"))
      (node (ref "LED104") (pin "2-VDD") (pinfunction "VDD_2-VDD") (pintype "power_in"))
      (node (ref "LED105") (pin "2-VDD") (pinfunction "VDD_2-VDD") (pintype "power_in"))
      (node (ref "LED11") (pin "2-VDD") (pinfunction "VDD_2-VDD") (pintype "power_in"))
      (node (ref "LED12") (pin "2-VDD") (pinfunction "VDD_2-VDD") (pintype "power_in"))
      (node (ref "LED13") (pin "2-VDD") (pinfunction "VDD_2-VDD") (pintype "power_in"))
      (node (ref "LED14") (pin "2-VDD") (pinfunction "VDD_2-VDD") (pintype "power_in"))
      (node (ref "LED15") (pin "2-VDD") (pinfunction "VDD_2-VDD") (pintype "power_in"))
      (node (ref "LED16") (pin "2-VDD") (pinfunction "VDD_2-VDD") (pintype "power_in"))
      (node (ref "LED17") (pin "2-VDD") (pinfunction "VDD_2-VDD") (pintype "power_in"))
      (node (ref "LED18") (pin "2-VDD") (pinfunction "VDD_2-VDD") (pintype "power_in"))
      (node (ref "LED19") (pin "2-VDD") (pinfunction "VDD_2-VDD") (pintype "power_in"))
      (node (ref "LED2") (pin "2-VDD") (pinfunction "VDD_2-VDD") (pintype "power_in"))
      (node (ref "LED20") (pin "2-VDD") (pinfunction "VDD_2-VDD") (pintype "power_in"))
      (node (ref "LED21") (pin "2-VDD") (pinfunction "VDD_2-VDD") (pintype "power_in"))
      (node (ref "LED22") (pin "2-VDD") (pinfunction "VDD_2-VDD") (pintype "power_in"))
      (node (ref "LED23") (pin "2-VDD") (pinfunction "VDD_2-VDD") (pintype "power_in"))
      (node (ref "LED24") (pin "2-VDD") (pinfunction "VDD_2-VDD") (pintype "power_in"))
      (node (ref "LED25") (pin "2-VDD") (pinfunction "VDD_2-VDD") (pintype "power_in"))
      (node (ref "LED26") (pin "2-VDD") (pinfunction "VDD_2-VDD") (pintype "power_in"))
      (node (ref "LED27") (pin "2-VDD") (pinfunction "VDD_2-VDD") (pintype "power_in"))
      (node (ref "LED28") (pin "2-VDD") (pinfunction "VDD_2-VDD") (pintype "power_in"))
      (node (ref "LED29") (pin "2-VDD") (pinfunction "VDD_2-VDD") (pintype "power_in"))
      (node (ref "LED3") (pin "2-VDD") (pinfunction "VDD_2-VDD") (pintype "power_in"))
      (node (ref "LED30") (pin "2-VDD") (pinfunction "VDD_2-VDD") (pintype "power_in"))
      (node (ref "LED31") (pin "2-VDD") (pinfunction "VDD_2-VDD") (pintype "power_in"))
      (node (ref "LED32") (pin "2-VDD") (pinfunction "VDD_2-VDD") (pintype "power_in"))
      (node (ref "LED33") (pin "2-VDD") (pinfunction "VDD_2-VDD") (pintype "power_in"))
      (node (ref "LED34") (pin "2-VDD") (pinfunction "VDD_2-VDD") (pintype "power_in"))
      (node (ref "LED35") (pin "2-VDD") (pinfunction "VDD_2-VDD") (pintype "power_in"))
      (node (ref "LED36") (pin "2-VDD") (pinfunction "VDD_2-VDD") (pintype "power_in"))
      (node (ref "LED37") (pin "2-VDD") (pinfunction "VDD_2-VDD") (pintype "power_in"))
      (node (ref "LED38") (pin "2-VDD") (pinfunction "VDD_2-VDD") (pintype "power_in"))
      (node (ref "LED39") (pin "2-VDD") (pinfunction "VDD_2-VDD") (pintype "power_in"))
      (node (ref "LED4") (pin "2-VDD") (pinfunction "VDD_2-VDD") (pintype "power_in"))
      (node (ref "LED40") (pin "2-VDD") (pinfunction "VDD_2-VDD") (pintype "power_in"))
      (node (ref "LED41") (pin "2-VDD") (pinfunction "VDD_2-VDD") (pintype "power_in"))
      (node (ref "LED42") (pin "2-VDD") (pinfunction "VDD_2-VDD") (pintype "power_in"))
      (node (ref "LED43") (pin "2-VDD") (pinfunction "VDD_2-VDD") (pintype "power_in"))
      (node (ref "LED44") (pin "2-VDD") (pinfunction "VDD_2-VDD") (pintype "power_in"))
      (node (ref "LED45") (pin "2-VDD") (pinfunction "VDD_2-VDD") (pintype "power_in"))
      (node (ref "LED46") (pin "2-VDD") (pinfunction "VDD_2-VDD") (pintype "power_in"))
      (node (ref "LED47") (pin "2-VDD") (pinfunction "VDD_2-VDD") (pintype "power_in"))
      (node (ref "LED48") (pin "2-VDD") (pinfunction "VDD_2-VDD") (pintype "power_in"))
      (node (ref "LED49") (pin "2-VDD") (pinfunction "VDD_2-VDD") (pintype "power_in"))
      (node (ref "LED5") (pin "2-VDD") (pinfunction "VDD_2-VDD") (pintype "power_in"))
      (node (ref "LED50") (pin "2-VDD") (pinfunction "VDD_2-VDD") (pintype "power_in"))
      (node (ref "LED51") (pin "2-VDD") (pinfunction "VDD_2-VDD") (pintype "power_in"))
      (node (ref "LED52") (pin "2-VDD") (pinfunction "VDD_2-VDD") (pintype "power_in"))
      (node (ref "LED53") (pin "2-VDD") (pinfunction "VDD_2-VDD") (pintype "power_in"))
      (node (ref "LED54") (pin "2-VDD") (pinfunction "VDD_2-VDD") (pintype "power_in"))
      (node (ref "LED55") (pin "2-VDD") (pinfunction "VDD_2-VDD") (pintype "power_in"))
      (node (ref "LED56") (pin "2-VDD") (pinfunction "VDD_2-VDD") (pintype "power_in"))
      (node (ref "LED57") (pin "2-VDD") (pinfunction "VDD_2-VDD") (pintype "power_in"))
      (node (ref "LED58") (pin "2-VDD") (pinfunction "VDD_2-VDD") (pintype "power_in"))
      (node (ref "LED59") (pin "2-VDD") (pinfunction "VDD_2-VDD") (pintype "power_in"))
      (node (ref "LED6") (pin "2-VDD") (pinfunction "VDD_2-VDD") (pintype "power_in"))
      (node (ref "LED60") (pin "2-VDD") (pinfunction "VDD_2-VDD") (pintype "power_in"))
      (node (ref "LED61") (pin "2-VDD") (pinfunction "VDD_2-VDD") (pintype "power_in"))
      (node (ref "LED62") (pin "2-VDD") (pinfunction "VDD_2-VDD") (pintype "power_in"))
      (node (ref "LED63") (pin "2-VDD") (pinfunction "VDD_2-VDD") (pintype "power_in"))
      (node (ref "LED64") (pin "2-VDD") (pinfunction "VDD_2-VDD") (pintype "power_in"))
      (node (ref "LED65") (pin "2-VDD") (pinfunction "VDD_2-VDD") (pintype "power_in"))
      (node (ref "LED66") (pin "2-VDD") (pinfunction "VDD_2-VDD") (pintype "power_in"))
      (node (ref "LED67") (pin "2-VDD") (pinfunction "VDD_2-VDD") (pintype "power_in"))
      (node (ref "LED68") (pin "2-VDD") (pinfunction "VDD_2-VDD") (pintype "power_in"))
      (node (ref "LED69") (pin "2-VDD") (pinfunction "VDD_2-VDD") (pintype "power_in"))
      (node (ref "LED7") (pin "2-VDD") (pinfunction "VDD_2-VDD") (pintype "power_in"))
      (node (ref "LED70") (pin "2-VDD") (pinfunction "VDD_2-VDD") (pintype "power_in"))
      (node (ref "LED71") (pin "2-VDD") (pinfunction "VDD_2-VDD") (pintype "power_in"))
      (node (ref "LED72") (pin "2-VDD") (pinfunction "VDD_2-VDD") (pintype "power_in"))
      (node (ref "LED73") (pin "2-VDD") (pinfunction "VDD_2-VDD") (pintype "power_in"))
      (node (ref "LED74") (pin "2-VDD") (pinfunction "VDD_2-VDD") (pintype "power_in"))
      (node (ref "LED75") (pin "2-VDD") (pinfunction "VDD_2-VDD") (pintype "power_in"))
      (node (ref "LED76") (pin "2-VDD") (pinfunction "VDD_2-VDD") (pintype "power_in"))
      (node (ref "LED77") (pin "2-VDD") (pinfunction "VDD_2-VDD") (pintype "power_in"))
      (node (ref "LED78") (pin "2-VDD") (pinfunction "VDD_2-VDD") (pintype "power_in"))
      (node (ref "LED79") (pin "2-VDD") (pinfunction "VDD_2-VDD") (pintype "power_in"))
      (node (ref "LED8") (pin "2-VDD") (pinfunction "VDD_2-VDD") (pintype "power_in"))
      (node (ref "LED80") (pin "2-VDD") (pinfunction "VDD_2-VDD") (pintype "power_in"))
      (node (ref "LED81") (pin "2-VDD") (pinfunction "VDD_2-VDD") (pintype "power_in"))
      (node (ref "LED82") (pin "2-VDD") (pinfunction "VDD_2-VDD") (pintype "power_in"))
      (node (ref "LED83") (pin "2-VDD") (pinfunction "VDD_2-VDD") (pintype "power_in"))
      (node (ref "LED84") (pin "2-VDD") (pinfunction "VDD_2-VDD") (pintype "power_in"))
      (node (ref "LED85") (pin "2-VDD") (pinfunction "VDD_2-VDD") (pintype "power_in"))
      (node (ref "LED86") (pin "2-VDD") (pinfunction "VDD_2-VDD") (pintype "power_in"))
      (node (ref "LED87") (pin "2-VDD") (pinfunction "VDD_2-VDD") (pintype "power_in"))
      (node (ref "LED88") (pin "2-VDD") (pinfunction "VDD_2-VDD") (pintype "power_in"))
      (node (ref "LED89") (pin "2-VDD") (pinfunction "VDD_2-VDD") (pintype "power_in"))
      (node (ref "LED9") (pin "2-VDD") (pinfunction "VDD_2-VDD") (pintype "power_in"))
      (node (ref "LED90") (pin "2-VDD") (pinfunction "VDD_2-VDD") (pintype "power_in"))
      (node (ref "LED91") (pin "2-VDD") (pinfunction "VDD_2-VDD") (pintype "power_in"))
      (node (ref "LED92") (pin "2-VDD") (pinfunction "VDD_2-VDD") (pintype "power_in"))
      (node (ref "LED93") (pin "2-VDD") (pinfunction "VDD_2-VDD") (pintype "power_in"))
      (node (ref "LED94") (pin "2-VDD") (pinfunction "VDD_2-VDD") (pintype "power_in"))
      (node (ref "LED95") (pin "2-VDD") (pinfunction "VDD_2-VDD") (pintype "power_in"))
      (node (ref "LED96") (pin "2-VDD") (pinfunction "VDD_2-VDD") (pintype "power_in"))
      (node (ref "LED97") (pin "2-VDD") (pinfunction "VDD_2-VDD") (pintype "power_in"))
      (node (ref "LED98") (pin "2-VDD") (pinfunction "VDD_2-VDD") (pintype "power_in"))
      (node (ref "LED99") (pin "2-VDD") (pinfunction "VDD_2-VDD") (pintype "power_in"))
      (node (ref "R6") (pin "2") (pinfunction "2_2") (pintype "passive"))
      (node (ref "ST1") (pin "1") (pinfunction "1_1") (pintype "bidirectional"))
      (node (ref "U$1") (pin "6") (pinfunction "VCCB_6") (pintype "power_in"))
    )
    (net (code "123") (name "VDDFF1") (class "Default")
      (node (ref "C4") (pin "P$1") (pinfunction "1_P$1") (pintype "passive"))
      (node (ref "F1") (pin "1") (pinfunction "1_1") (pintype "passive"))
      (node (ref "L1") (pin "P$1") (pinfunction "1_P$1") (pintype "passive"))
    )
    (net (code "124") (name "VDDFF2") (class "Default")
      (node (ref "C3") (pin "P$1") (pinfunction "1_P$1") (pintype "passive"))
      (node (ref "F2") (pin "1") (pinfunction "1_1") (pintype "passive"))
      (node (ref "L2") (pin "P$1") (pinfunction "1_P$1") (pintype "passive"))
    )
    (net (code "125") (name "unconnected-(CON1-D+1-PadA6)") (class "Default")
      (node (ref "CON1") (pin "A6") (pinfunction "D+1_A6") (pintype "passive"))
    )
    (net (code "126") (name "unconnected-(CON1-D+2-PadB6)") (class "Default")
      (node (ref "CON1") (pin "B6") (pinfunction "D+2_B6") (pintype "passive"))
    )
    (net (code "127") (name "unconnected-(CON1-D-1-PadA7)") (class "Default")
      (node (ref "CON1") (pin "A7") (pinfunction "D-1_A7") (pintype "passive"))
    )
    (net (code "128") (name "unconnected-(CON1-D-2-PadB7)") (class "Default")
      (node (ref "CON1") (pin "B7") (pinfunction "D-2_B7") (pintype "passive"))
    )
    (net (code "129") (name "unconnected-(CON1-SBU1-PadA8)") (class "Default")
      (node (ref "CON1") (pin "A8") (pinfunction "SBU1_A8") (pintype "passive"))
    )
    (net (code "130") (name "unconnected-(CON1-SBU2-PadB8)") (class "Default")
      (node (ref "CON1") (pin "B8") (pinfunction "SBU2_B8") (pintype "passive"))
    )
    (net (code "131") (name "unconnected-(MS1-AREF-Pad3)") (class "Default")
      (node (ref "MS1") (pin "3") (pinfunction "AREF_3") (pintype "passive"))
    )
    (net (code "132") (name "unconnected-(MS1-EN-Pad27)") (class "Default")
      (node (ref "MS1") (pin "27") (pinfunction "EN_27") (pintype "passive"))
    )
    (net (code "133") (name "unconnected-(MS1-GPIO9-Pad21)") (class "Default")
      (node (ref "MS1") (pin "21") (pinfunction "GPIO9_21") (pintype "bidirectional"))
    )
    (net (code "134") (name "unconnected-(MS1-GPIO10-Pad22)") (class "Default")
      (node (ref "MS1") (pin "22") (pinfunction "GPIO10_22") (pintype "bidirectional"))
    )
    (net (code "135") (name "unconnected-(MS1-GPIO11-Pad23)") (class "Default")
      (node (ref "MS1") (pin "23") (pinfunction "GPIO11_23") (pintype "bidirectional"))
    )
    (net (code "136") (name "unconnected-(MS1-GPIO13-Pad25)") (class "Default")
      (node (ref "MS1") (pin "25") (pinfunction "GPIO13_25") (pintype "bidirectional"))
    )
    (net (code "137") (name "unconnected-(MS1-GPIOA0-Pad5)") (class "Default")
      (node (ref "MS1") (pin "5") (pinfunction "GPIOA0_5") (pintype "bidirectional"))
    )
    (net (code "138") (name "unconnected-(MS1-GPIOA1-Pad6)") (class "Default")
      (node (ref "MS1") (pin "6") (pinfunction "GPIOA1_6") (pintype "bidirectional"))
    )
    (net (code "139") (name "unconnected-(MS1-GPIOA2-Pad7)") (class "Default")
      (node (ref "MS1") (pin "7") (pinfunction "GPIOA2_7") (pintype "bidirectional"))
    )
    (net (code "140") (name "unconnected-(MS1-GPIOA3-Pad8)") (class "Default")
      (node (ref "MS1") (pin "8") (pinfunction "GPIOA3_8") (pintype "bidirectional"))
    )
    (net (code "141") (name "unconnected-(MS1-GPIOA4-Pad9)") (class "Default")
      (node (ref "MS1") (pin "9") (pinfunction "GPIOA4_9") (pintype "bidirectional"))
    )
    (net (code "142") (name "unconnected-(MS1-GPIOA5-Pad10)") (class "Default")
      (node (ref "MS1") (pin "10") (pinfunction "GPIOA5_10") (pintype "bidirectional"))
    )
    (net (code "143") (name "unconnected-(MS1-GPIOMISO-Pad13)") (class "Default")
      (node (ref "MS1") (pin "13") (pinfunction "GPIOMISO_13") (pintype "bidirectional"))
    )
    (net (code "144") (name "unconnected-(MS1-GPIORX-Pad14)") (class "Default")
      (node (ref "MS1") (pin "14") (pinfunction "GPIORX_14") (pintype "bidirectional"))
    )
    (net (code "145") (name "unconnected-(MS1-GPIOSCK-Pad11)") (class "Default")
      (node (ref "MS1") (pin "11") (pinfunction "GPIOSCK_11") (pintype "bidirectional"))
    )
    (net (code "146") (name "unconnected-(MS1-GPIOSCL-Pad18)") (class "Default")
      (node (ref "MS1") (pin "18") (pinfunction "GPIOSCL_18") (pintype "bidirectional"))
    )
    (net (code "147") (name "unconnected-(MS1-GPIOSDA-Pad17)") (class "Default")
      (node (ref "MS1") (pin "17") (pinfunction "GPIOSDA_17") (pintype "bidirectional"))
    )
    (net (code "148") (name "unconnected-(MS1-GPIOTX-Pad15)") (class "Default")
      (node (ref "MS1") (pin "15") (pinfunction "GPIOTX_15") (pintype "bidirectional"))
    )
    (net (code "149") (name "unconnected-(MS1-NC-Pad16)") (class "Default")
      (node (ref "MS1") (pin "16") (pinfunction "NC_16") (pintype "passive"))
    )
    (net (code "150") (name "{slash}RESET") (class "Default")
      (node (ref "MS1") (pin "1") (pinfunction "~{RESET}_1") (pintype "input"))
      (node (ref "S1") (pin "1") (pinfunction "1_1") (pintype "passive"))
      (node (ref "S1") (pin "2") (pinfunction "2_2") (pintype "passive"))
      (node (ref "S1") (pin "7") (pinfunction "1_7") (pintype "passive"))
      (node (ref "S1") (pin "8") (pinfunction "2_8") (pintype "passive"))
    )
  )
)
